# EM2.net
KiCad netlist of a schematic drawn in EAGLE
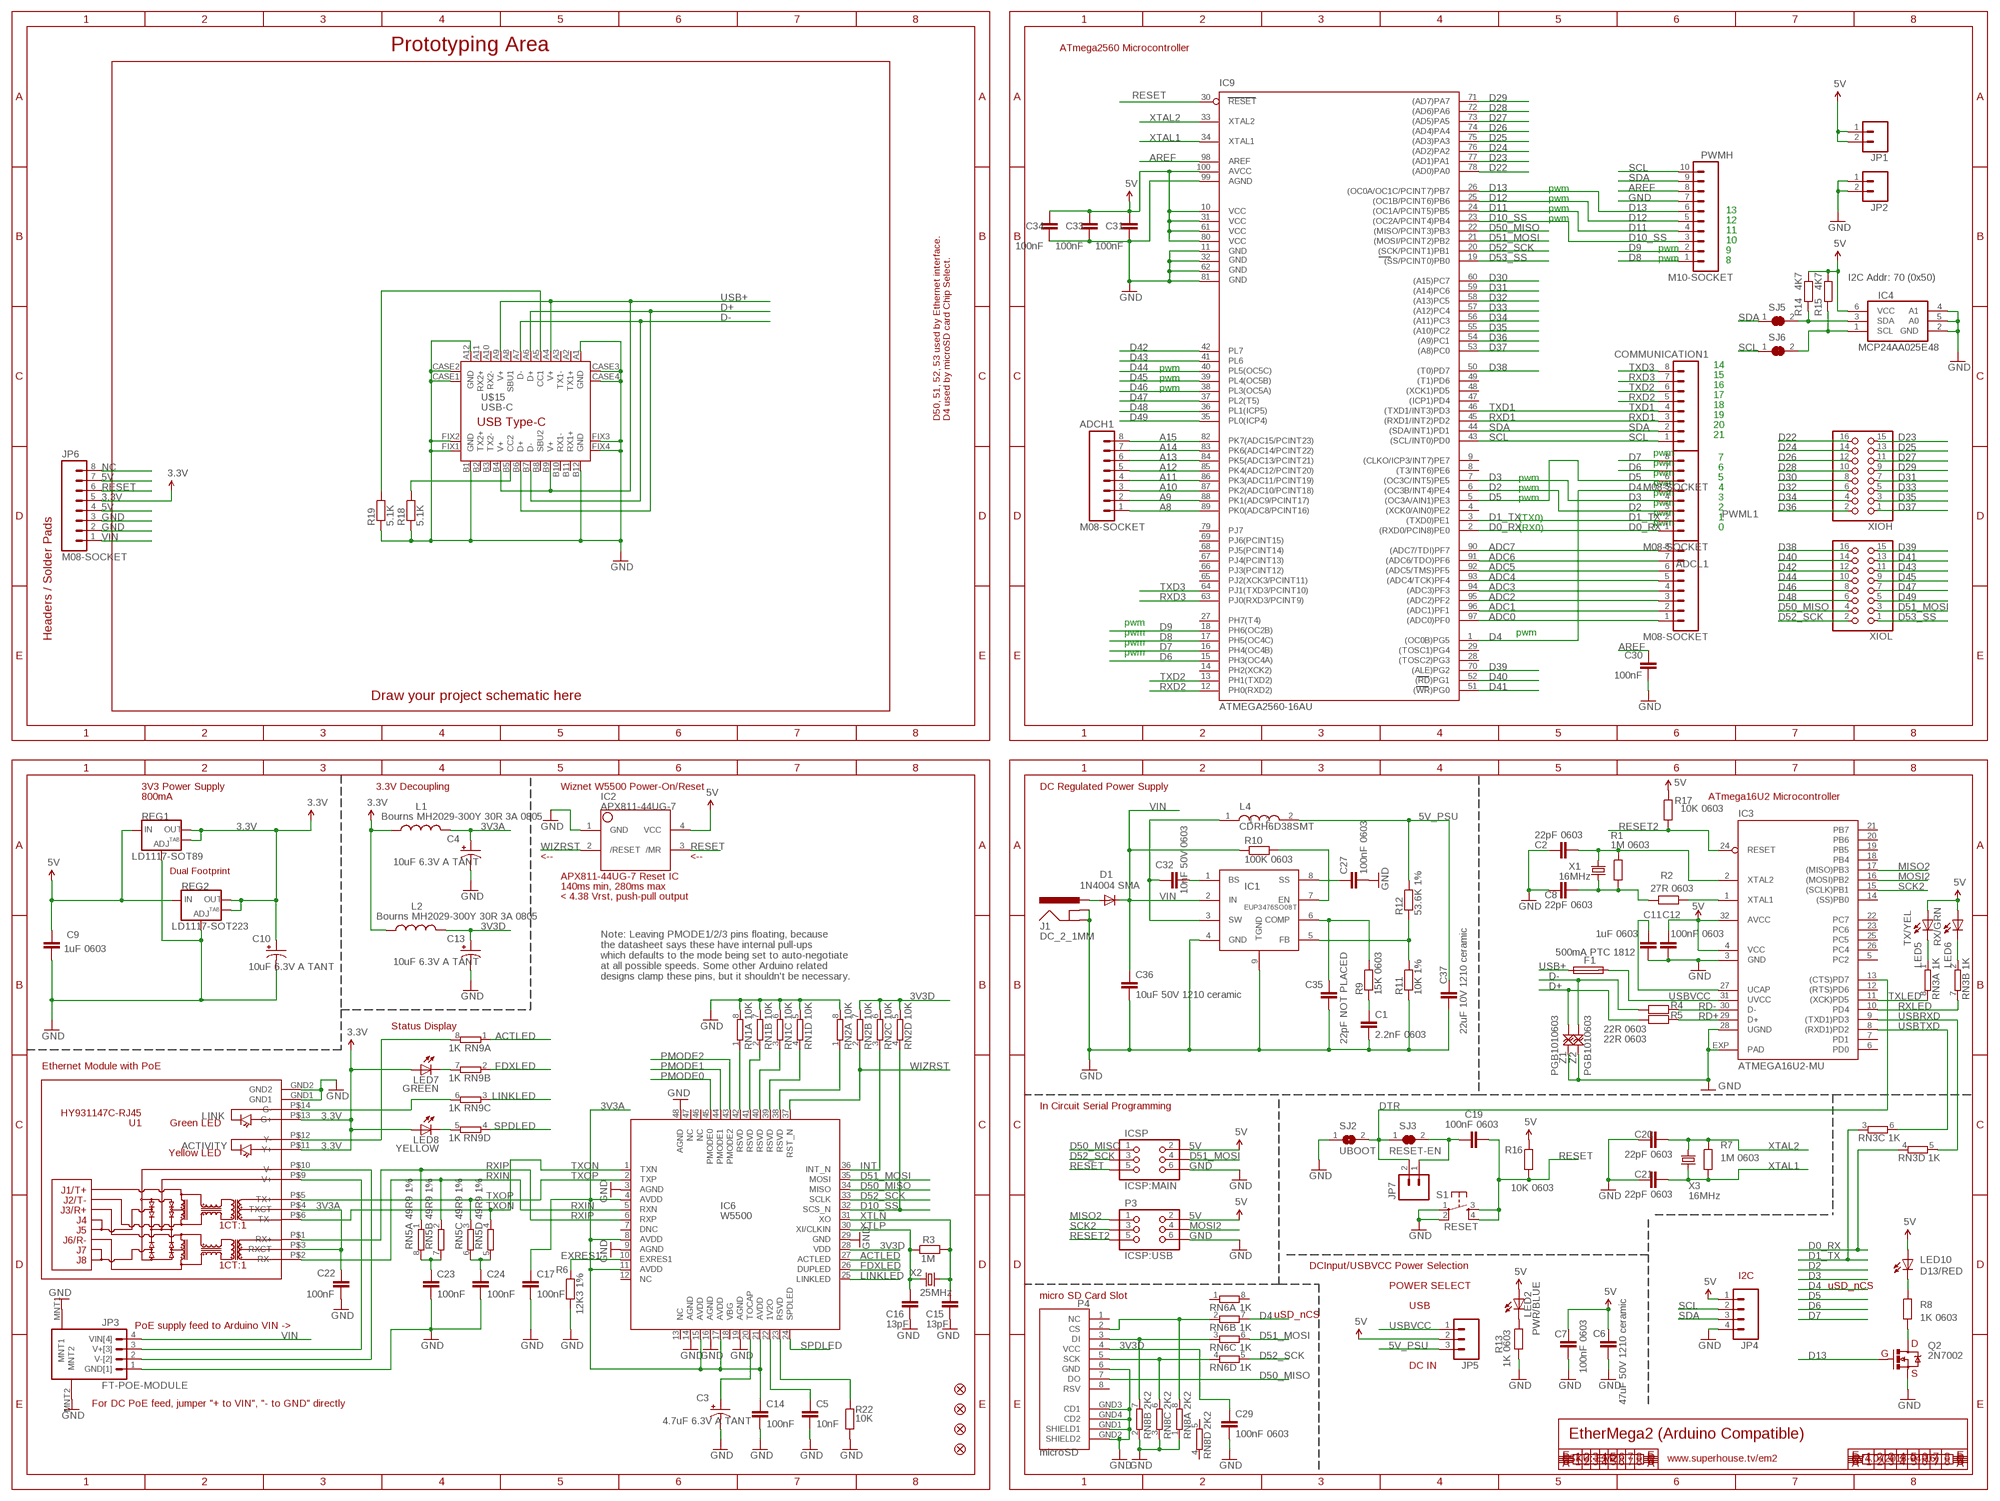
[diagram p0: schematic, sheet 1]

(export (version "E")
  (design (tool "Eeschema 10.0.6"))
  (components
    (comp (ref "ADCH1")
      (value "M08-SOCKET")
      (footprint "eagle-import:1X08-S")
      (libsource (lib "eagle-import") (part "M08-SOCKET"))
    )
    (comp (ref "ADCL1")
      (value "M08-SOCKET")
      (footprint "eagle-import:1X08-S")
      (libsource (lib "eagle-import") (part "M08-SOCKET"))
    )
    (comp (ref "C1")
      (value "2.2nF 0603")
      (footprint "eagle-import:C0603")
      (libsource (lib "eagle-import") (part "CAP0603"))
    )
    (comp (ref "C2")
      (value "22pF 0603")
      (footprint "eagle-import:C0603")
      (libsource (lib "eagle-import") (part "CAP0603"))
    )
    (comp (ref "C3")
      (value "4.7uF 6.3V A TANT")
      (footprint "eagle-import:EIA3216")
      (libsource (lib "eagle-import") (part "CAP_POL1206"))
    )
    (comp (ref "C4")
      (value "10uF 6.3V A TANT")
      (footprint "eagle-import:EIA3216")
      (libsource (lib "eagle-import") (part "CAP_POL1206"))
    )
    (comp (ref "C5")
      (value "10nF")
      (footprint "eagle-import:C0603")
      (libsource (lib "eagle-import") (part "CAP0603"))
    )
    (comp (ref "C6")
      (value "47uF 50V 1210 ceramic")
      (footprint "eagle-import:C1210")
      (libsource (lib "eagle-import") (part "C-EUC1210"))
    )
    (comp (ref "C7")
      (value "100nF 0603")
      (footprint "eagle-import:C0603")
      (libsource (lib "eagle-import") (part "CAP0603"))
    )
    (comp (ref "C8")
      (value "22pF 0603")
      (footprint "eagle-import:C0603")
      (libsource (lib "eagle-import") (part "CAP0603"))
    )
    (comp (ref "C9")
      (value "1uF 0603")
      (footprint "eagle-import:C0603")
      (libsource (lib "eagle-import") (part "CAP0603"))
    )
    (comp (ref "C10")
      (value "10uF 6.3V A TANT")
      (footprint "eagle-import:EIA3216")
      (libsource (lib "eagle-import") (part "CAP_POL1206"))
    )
    (comp (ref "C11")
      (value "1uF 0603")
      (footprint "eagle-import:C0603")
      (libsource (lib "eagle-import") (part "CAP0603"))
    )
    (comp (ref "C12")
      (value "100nF 0603")
      (footprint "eagle-import:C0603")
      (libsource (lib "eagle-import") (part "CAP0603"))
    )
    (comp (ref "C13")
      (value "10uF 6.3V A TANT")
      (footprint "eagle-import:EIA3216")
      (libsource (lib "eagle-import") (part "CAP_POL1206"))
    )
    (comp (ref "C14")
      (value "100nF")
      (footprint "eagle-import:C0603")
      (libsource (lib "eagle-import") (part "CAP0603"))
    )
    (comp (ref "C15")
      (value "13pF")
      (footprint "eagle-import:C0603")
      (libsource (lib "eagle-import") (part "CAP0603"))
    )
    (comp (ref "C16")
      (value "13pF")
      (footprint "eagle-import:C0603")
      (libsource (lib "eagle-import") (part "CAP0603"))
    )
    (comp (ref "C17")
      (value "100nF")
      (footprint "eagle-import:C0603")
      (libsource (lib "eagle-import") (part "CAP0603"))
    )
    (comp (ref "C19")
      (value "100nF 0603")
      (footprint "eagle-import:C0603")
      (libsource (lib "eagle-import") (part "CAP0603"))
    )
    (comp (ref "C20")
      (value "22pF 0603")
      (footprint "eagle-import:C0603")
      (libsource (lib "eagle-import") (part "CAP0603"))
    )
    (comp (ref "C21")
      (value "22pF 0603")
      (footprint "eagle-import:C0603")
      (libsource (lib "eagle-import") (part "CAP0603"))
    )
    (comp (ref "C22")
      (value "100nF")
      (footprint "eagle-import:C0603")
      (libsource (lib "eagle-import") (part "CAP0603"))
    )
    (comp (ref "C23")
      (value "100nF")
      (footprint "eagle-import:C0603")
      (libsource (lib "eagle-import") (part "CAP0603"))
    )
    (comp (ref "C24")
      (value "100nF")
      (footprint "eagle-import:C0603")
      (libsource (lib "eagle-import") (part "CAP0603"))
    )
    (comp (ref "C27")
      (value "100nF 0603")
      (footprint "eagle-import:C0603")
      (libsource (lib "eagle-import") (part "CAP0603"))
    )
    (comp (ref "C29")
      (value "100nF 0603")
      (footprint "eagle-import:C0603")
      (libsource (lib "eagle-import") (part "CAP0603"))
    )
    (comp (ref "C30")
      (value "100nF")
      (footprint "eagle-import:C0603")
      (libsource (lib "eagle-import") (part "CAP0603"))
    )
    (comp (ref "C31")
      (value "100nF")
      (footprint "eagle-import:C0603")
      (libsource (lib "eagle-import") (part "CAP0603"))
    )
    (comp (ref "C32")
      (value "10nF 50V 0603")
      (footprint "eagle-import:C0603")
      (libsource (lib "eagle-import") (part "CAP0603"))
    )
    (comp (ref "C33")
      (value "100nF")
      (footprint "eagle-import:C0603")
      (libsource (lib "eagle-import") (part "CAP0603"))
    )
    (comp (ref "C34")
      (value "100nF")
      (footprint "eagle-import:C0603")
      (libsource (lib "eagle-import") (part "CAP0603"))
    )
    (comp (ref "C35")
      (value "22pF NOT PLACED")
      (footprint "eagle-import:C0603")
      (libsource (lib "eagle-import") (part "CAP0603"))
    )
    (comp (ref "C36")
      (value "10uF 50V 1210 ceramic")
      (footprint "eagle-import:C1210")
      (libsource (lib "eagle-import") (part "C-EUC1210"))
    )
    (comp (ref "C37")
      (value "22uF 10V 1210 ceramic")
      (footprint "eagle-import:C1210")
      (libsource (lib "eagle-import") (part "C-EUC1210"))
    )
    (comp (ref "COMMUNICATION1")
      (value "M08-SOCKET")
      (footprint "eagle-import:1X08-S")
      (libsource (lib "eagle-import") (part "M08-SOCKET"))
    )
    (comp (ref "D1")
      (value "1N4004 SMA")
      (footprint "eagle-import:SMA-DIODE")
      (libsource (lib "eagle-import") (part "DIODESMA"))
    )
    (comp (ref "F1")
      (value "500mA PTC 1812")
      (footprint "eagle-import:1812")
      (libsource (lib "eagle-import") (part "PTC050"))
    )
    (comp (ref "FID1")
      (value "FIDUCIAL1X2.5")
      (footprint "eagle-import:FIDUCIAL-1X2.5")
      (libsource (lib "eagle-import") (part "FIDUCIAL1X2.5"))
    )
    (comp (ref "FID2")
      (value "FIDUCIAL1X2.5")
      (footprint "eagle-import:FIDUCIAL-1X2.5")
      (libsource (lib "eagle-import") (part "FIDUCIAL1X2.5"))
    )
    (comp (ref "FID3")
      (value "FIDUCIAL1X2.5")
      (footprint "eagle-import:FIDUCIAL-1X2.5")
      (libsource (lib "eagle-import") (part "FIDUCIAL1X2.5"))
    )
    (comp (ref "FID4")
      (value "FIDUCIAL1X2.5")
      (footprint "eagle-import:FIDUCIAL-1X2.5")
      (libsource (lib "eagle-import") (part "FIDUCIAL1X2.5"))
    )
    (comp (ref "IC1")
      (value "EUP3476SO08T")
      (footprint "eagle-import:SO08T")
      (libsource (lib "eagle-import") (part "EUP3476SO08T"))
    )
    (comp (ref "IC2")
      (value "APX811-44UG-7")
      (footprint "eagle-import:SOT143-R")
      (libsource (lib "eagle-import") (part "APX81X-RESET-IC"))
    )
    (comp (ref "IC3")
      (value "ATMEGA16U2-MU")
      (footprint "eagle-import:ATMEL_QFN32")
      (libsource (lib "eagle-import") (part "ATMEL_ATMEGA8U2-MUQFN"))
    )
    (comp (ref "IC4")
      (value "MCP24AA025E48")
      (footprint "eagle-import:SOT23-6")
      (libsource (lib "eagle-import") (part "MCP24AA025E48"))
    )
    (comp (ref "IC6")
      (value "W5500")
      (footprint "eagle-import:W5500")
      (libsource (lib "eagle-import") (part "W5500"))
    )
    (comp (ref "IC9")
      (value "ATMEGA2560-16AU")
      (footprint "eagle-import:TQFP100")
      (libsource (lib "eagle-import") (part "ATMEGA2560AU2560-16"))
    )
    (comp (ref "ICSP")
      (value "ICSP:MAIN")
      (footprint "eagle-import:2X03-ICSP")
      (libsource (lib "eagle-import") (part "ICSP-PIN"))
    )
    (comp (ref "J1")
      (value "DC_2_1MM")
      (footprint "eagle-import:POWER_JACK_SLOTS")
      (libsource (lib "eagle-import") (part "POWER_JACK-SLOTS"))
    )
    (comp (ref "JP1")
      (value "M02PTH")
      (footprint "eagle-import:1X02")
      (libsource (lib "eagle-import") (part "M02PTH"))
    )
    (comp (ref "JP2")
      (value "M02PTH")
      (footprint "eagle-import:1X02")
      (libsource (lib "eagle-import") (part "M02PTH"))
    )
    (comp (ref "JP3")
      (value "FT-POE-MODULE")
      (footprint "eagle-import:FT-POE-MODULE-CLEAN")
      (libsource (lib "eagle-import") (part "FT-POE-MODULE2"))
    )
    (comp (ref "JP4")
      (value "M04PTH")
      (footprint "eagle-import:1X04")
      (libsource (lib "eagle-import") (part "M04PTH"))
    )
    (comp (ref "JP5")
      (value "M03-PIN")
      (footprint "eagle-import:1X03-P")
      (libsource (lib "eagle-import") (part "M03-PIN"))
    )
    (comp (ref "JP6")
      (value "M08-SOCKET")
      (footprint "eagle-import:1X08-S")
      (libsource (lib "eagle-import") (part "M08-SOCKET"))
    )
    (comp (ref "JP7")
      (value "M02PTH")
      (footprint "eagle-import:1X02")
      (libsource (lib "eagle-import") (part "freetronics-master-v1.1_M02PTH"))
    )
    (comp (ref "L1")
      (value "Bourns MH2029-300Y 30R 3A 0805")
      (footprint "eagle-import:L2012C")
      (libsource (lib "eagle-import") (part "L-USL2012C"))
    )
    (comp (ref "L2")
      (value "Bourns MH2029-300Y 30R 3A 0805")
      (footprint "eagle-import:L2012C")
      (libsource (lib "eagle-import") (part "L-USL2012C"))
    )
    (comp (ref "L4")
      (value "CDRH6D38SMT")
      (footprint "eagle-import:CDRH")
      (libsource (lib "eagle-import") (part "CDRH6D38SMT"))
    )
    (comp (ref "LED2")
      (value "PWR/BLUE")
      (footprint "eagle-import:LED-0603")
      (libsource (lib "eagle-import") (part "LED0603"))
    )
    (comp (ref "LED5")
      (value "TX/YEL")
      (footprint "eagle-import:LED-0603")
      (libsource (lib "eagle-import") (part "LED0603"))
    )
    (comp (ref "LED6")
      (value "RX/GRN")
      (footprint "eagle-import:LED-0603")
      (libsource (lib "eagle-import") (part "LED0603"))
    )
    (comp (ref "LED7")
      (value "GREEN")
      (footprint "eagle-import:LED-0603")
      (libsource (lib "eagle-import") (part "LED0603"))
    )
    (comp (ref "LED8")
      (value "YELLOW")
      (footprint "eagle-import:LED-0603")
      (libsource (lib "eagle-import") (part "LED0603"))
    )
    (comp (ref "LED10")
      (value "D13/RED")
      (footprint "eagle-import:LED-0603")
      (libsource (lib "eagle-import") (part "LED0603"))
    )
    (comp (ref "P3")
      (value "ICSP:USB")
      (footprint "eagle-import:2X03-ICSP")
      (libsource (lib "eagle-import") (part "ICSP-PIN"))
    )
    (comp (ref "P4")
      (value "microSD")
      (footprint "eagle-import:MOLEX-SD-500901-003")
      (libsource (lib "eagle-import") (part "USD-SOCKETHINGE"))
    )
    (comp (ref "PWMH")
      (value "M10-SOCKET")
      (footprint "eagle-import:1X10-S")
      (libsource (lib "eagle-import") (part "M10-SOCKET"))
    )
    (comp (ref "PWML1")
      (value "M08-SOCKET")
      (footprint "eagle-import:1X08-S")
      (libsource (lib "eagle-import") (part "M08-SOCKET"))
    )
    (comp (ref "Q2")
      (value "2N7002")
      (footprint "eagle-import:SOT23-3")
      (libsource (lib "eagle-import") (part "MOSFET-NCHANNEL-233"))
    )
    (comp (ref "R1")
      (value "1M 0603")
      (footprint "eagle-import:R0603")
      (libsource (lib "eagle-import") (part "RESISTOR0603"))
    )
    (comp (ref "R2")
      (value "27R 0603")
      (footprint "eagle-import:R0603")
      (libsource (lib "eagle-import") (part "RESISTOR0603"))
    )
    (comp (ref "R3")
      (value "1M")
      (footprint "eagle-import:R0603")
      (libsource (lib "eagle-import") (part "RESISTOR0603"))
    )
    (comp (ref "R4")
      (value "22R 0603")
      (footprint "eagle-import:R0603")
      (libsource (lib "eagle-import") (part "RESISTOR0603"))
    )
    (comp (ref "R5")
      (value "22R 0603")
      (footprint "eagle-import:R0603")
      (libsource (lib "eagle-import") (part "RESISTOR0603"))
    )
    (comp (ref "R6")
      (value "12K3 1%")
      (footprint "eagle-import:R0603")
      (libsource (lib "eagle-import") (part "RESISTOR0603"))
    )
    (comp (ref "R7")
      (value "1M 0603")
      (footprint "eagle-import:R0603")
      (libsource (lib "eagle-import") (part "RESISTOR0603"))
    )
    (comp (ref "R8")
      (value "1K 0603")
      (footprint "eagle-import:R0603")
      (libsource (lib "eagle-import") (part "RESISTOR0603"))
    )
    (comp (ref "R9")
      (value "15K 0603")
      (footprint "eagle-import:R0603")
      (libsource (lib "eagle-import") (part "RESISTOR0603"))
    )
    (comp (ref "R10")
      (value "100K 0603")
      (footprint "eagle-import:R0603")
      (libsource (lib "eagle-import") (part "RESISTOR0603"))
    )
    (comp (ref "R11")
      (value "10K 1%")
      (footprint "eagle-import:R0603")
      (libsource (lib "eagle-import") (part "RESISTOR0603"))
    )
    (comp (ref "R12")
      (value "53.6K 1%")
      (footprint "eagle-import:R0603")
      (libsource (lib "eagle-import") (part "RESISTOR0603"))
    )
    (comp (ref "R13")
      (value "1K 0603")
      (footprint "eagle-import:R0603")
      (libsource (lib "eagle-import") (part "RESISTOR0603"))
    )
    (comp (ref "R14")
      (value "4K7")
      (footprint "eagle-import:R0603")
      (libsource (lib "eagle-import") (part "RESISTOR0603"))
    )
    (comp (ref "R15")
      (value "4K7")
      (footprint "eagle-import:R0603")
      (libsource (lib "eagle-import") (part "RESISTOR0603"))
    )
    (comp (ref "R16")
      (value "10K 0603")
      (footprint "eagle-import:R0603")
      (libsource (lib "eagle-import") (part "RESISTOR0603"))
    )
    (comp (ref "R17")
      (value "10K 0603")
      (footprint "eagle-import:R0603")
      (libsource (lib "eagle-import") (part "RESISTOR0603"))
    )
    (comp (ref "R18")
      (value "5.1K")
      (footprint "eagle-import:R0603")
      (libsource (lib "eagle-import") (part "RESISTOR0603"))
    )
    (comp (ref "R19")
      (value "5.1K")
      (footprint "eagle-import:R0603")
      (libsource (lib "eagle-import") (part "RESISTOR0603"))
    )
    (comp (ref "R22")
      (value "10K")
      (footprint "eagle-import:R0603")
      (libsource (lib "eagle-import") (part "RESISTOR0603"))
    )
    (comp (ref "REG1")
      (value "LD1117-SOT89")
      (footprint "eagle-import:SOT89")
      (libsource (lib "eagle-import") (part "V_REG_LM1117SOT89"))
    )
    (comp (ref "REG2")
      (value "LD1117-SOT223")
      (footprint "eagle-import:SOT223")
      (libsource (lib "eagle-import") (part "V_REG_LM1117SOT223"))
    )
    (comp (ref "RN1")
      (value "10K")
      (footprint "eagle-import:CAY16")
      (libsource (lib "eagle-import") (part "4R-NCAY16"))
    )
    (comp (ref "RN2")
      (value "10K")
      (footprint "eagle-import:CAY16")
      (libsource (lib "eagle-import") (part "4R-NCAY16"))
    )
    (comp (ref "RN3")
      (value "1K")
      (footprint "eagle-import:CAY16")
      (libsource (lib "eagle-import") (part "4R-NCAY16"))
    )
    (comp (ref "RN5")
      (value "49R9 1%")
      (footprint "eagle-import:CAY16")
      (libsource (lib "eagle-import") (part "4R-NCAY16"))
    )
    (comp (ref "RN6")
      (value "1K")
      (footprint "eagle-import:CAY16")
      (libsource (lib "eagle-import") (part "4R-NCAY16"))
    )
    (comp (ref "RN8")
      (value "2K2")
      (footprint "eagle-import:CAY16")
      (libsource (lib "eagle-import") (part "4R-NCAY16"))
    )
    (comp (ref "RN9")
      (value "1K")
      (footprint "eagle-import:CAY16")
      (libsource (lib "eagle-import") (part "4R-NCAY16"))
    )
    (comp (ref "S1")
      (value "RESET")
      (footprint "eagle-import:TACTILE_SMT-6MM")
      (libsource (lib "eagle-import") (part "TAC_SWITCH-SMT-6"))
    )
    (comp (ref "SJ2")
      (value "UBOOT")
      (footprint "eagle-import:SJ")
      (libsource (lib "eagle-import") (part "SJ"))
    )
    (comp (ref "SJ3")
      (value "RESET-EN")
      (footprint "eagle-import:SJC")
      (libsource (lib "eagle-import") (part "SJCN"))
    )
    (comp (ref "SJ5")
      (value "SJCN")
      (footprint "eagle-import:SJC")
      (libsource (lib "eagle-import") (part "SJCN"))
    )
    (comp (ref "SJ6")
      (value "SJCN")
      (footprint "eagle-import:SJC")
      (libsource (lib "eagle-import") (part "SJCN"))
    )
    (comp (ref "U$15")
      (value "USB-C")
      (footprint "eagle-import:USB-C-U52A")
      (libsource (lib "eagle-import") (part "USB-C"))
    )
    (comp (ref "U1")
      (value "HY931147C-RJ45")
      (footprint "eagle-import:HY931147C")
      (libsource (lib "eagle-import") (part "HY931147C-RJ45"))
    )
    (comp (ref "X1")
      (value "16MHz")
      (footprint "eagle-import:HC49U-V")
      (libsource (lib "eagle-import") (part "CRYSTALHC49UV"))
    )
    (comp (ref "X2")
      (value "25MHz")
      (footprint "eagle-import:HC49U-V")
      (libsource (lib "eagle-import") (part "CRYSTALHC49UV"))
    )
    (comp (ref "X3")
      (value "16MHz")
      (footprint "eagle-import:HC49U-V")
      (libsource (lib "eagle-import") (part "CRYSTALHC49UV"))
    )
    (comp (ref "XIOH")
      (value "PINHD-2X8")
      (footprint "eagle-import:2X08")
      (libsource (lib "eagle-import") (part "PINHD-2X8"))
    )
    (comp (ref "XIOL")
      (value "PINHD-2X8")
      (footprint "eagle-import:2X08")
      (libsource (lib "eagle-import") (part "PINHD-2X8"))
    )
    (comp (ref "Z1")
      (value "PGB1010603")
      (footprint "eagle-import:TVS0603")
      (libsource (lib "eagle-import") (part "TVS0603"))
    )
    (comp (ref "Z2")
      (value "PGB1010603")
      (footprint "eagle-import:TVS0603")
      (libsource (lib "eagle-import") (part "TVS0603"))
    )
  )
  (nets
    (net (code "1") (name "/3V3A") (class "Default")
      (node (ref "C14") (pin "1") (pinfunction "1_1") (pintype "passive"))
      (node (ref "C17") (pin "1") (pinfunction "1_1") (pintype "passive"))
      (node (ref "C22") (pin "1") (pinfunction "1_1") (pintype "passive"))
      (node (ref "C4") (pin "A") (pinfunction "+_A") (pintype "passive"))
      (node (ref "IC6") (pin "11") (pinfunction "AVDD_11") (pintype "passive"))
      (node (ref "IC6") (pin "15") (pinfunction "AVDD_15") (pintype "passive"))
      (node (ref "IC6") (pin "17") (pinfunction "AVDD_17") (pintype "passive"))
      (node (ref "IC6") (pin "21") (pinfunction "AVDD_21") (pintype "passive"))
      (node (ref "IC6") (pin "4") (pinfunction "AVDD_4") (pintype "passive"))
      (node (ref "IC6") (pin "8") (pinfunction "AVDD_8") (pintype "passive"))
      (node (ref "L1") (pin "2") (pinfunction "2_2") (pintype "passive"))
      (node (ref "U1") (pin "P$3") (pinfunction "RXCT_P$3") (pintype "bidirectional"))
      (node (ref "U1") (pin "P$4") (pinfunction "TXCT_P$4") (pintype "bidirectional"))
    )
    (net (code "2") (name "/3V3D") (class "Default")
      (node (ref "C13") (pin "A") (pinfunction "+_A") (pintype "passive"))
      (node (ref "C29") (pin "1") (pinfunction "1_1") (pintype "passive"))
      (node (ref "IC6") (pin "28") (pinfunction "VDD_28") (pintype "passive"))
      (node (ref "L2") (pin "2") (pinfunction "2_2") (pintype "passive"))
      (node (ref "P4") (pin "4") (pinfunction "VCC_4") (pintype "bidirectional"))
      (node (ref "RN2") (pin "5") (pinfunction "2_5") (pintype "passive"))
      (node (ref "RN2") (pin "6") (pinfunction "2_6") (pintype "passive"))
      (node (ref "RN2") (pin "7") (pinfunction "2_7") (pintype "passive"))
    )
    (net (code "3") (name "/5V_PSU") (class "Default")
      (node (ref "C37") (pin "1") (pinfunction "1_1") (pintype "passive"))
      (node (ref "JP5") (pin "3") (pinfunction "3_3") (pintype "passive"))
      (node (ref "L4") (pin "2") (pinfunction "2_2") (pintype "bidirectional"))
      (node (ref "R12") (pin "2") (pinfunction "2_2") (pintype "passive"))
    )
    (net (code "4") (name "/A8") (class "Default")
      (node (ref "ADCH1") (pin "1") (pinfunction "1_1") (pintype "passive"))
      (node (ref "IC9") (pin "89") (pinfunction "PK0(ADC8/PCINT16)_89") (pintype "bidirectional"))
    )
    (net (code "5") (name "/A9") (class "Default")
      (node (ref "ADCH1") (pin "2") (pinfunction "2_2") (pintype "passive"))
      (node (ref "IC9") (pin "88") (pinfunction "PK1(ADC9/PCINT17)_88") (pintype "bidirectional"))
    )
    (net (code "6") (name "/A10") (class "Default")
      (node (ref "ADCH1") (pin "3") (pinfunction "3_3") (pintype "passive"))
      (node (ref "IC9") (pin "87") (pinfunction "PK2(ADC10/PCINT18)_87") (pintype "bidirectional"))
    )
    (net (code "7") (name "/A11") (class "Default")
      (node (ref "ADCH1") (pin "4") (pinfunction "4_4") (pintype "passive"))
      (node (ref "IC9") (pin "86") (pinfunction "PK3(ADC11/PCINT19)_86") (pintype "bidirectional"))
    )
    (net (code "8") (name "/A12") (class "Default")
      (node (ref "ADCH1") (pin "5") (pinfunction "5_5") (pintype "passive"))
      (node (ref "IC9") (pin "85") (pinfunction "PK4(ADC12/PCINT20)_85") (pintype "bidirectional"))
    )
    (net (code "9") (name "/A13") (class "Default")
      (node (ref "ADCH1") (pin "6") (pinfunction "6_6") (pintype "passive"))
      (node (ref "IC9") (pin "84") (pinfunction "PK5(ADC13/PCINT21)_84") (pintype "bidirectional"))
    )
    (net (code "10") (name "/A14") (class "Default")
      (node (ref "ADCH1") (pin "7") (pinfunction "7_7") (pintype "passive"))
      (node (ref "IC9") (pin "83") (pinfunction "PK6(ADC14/PCINT22)_83") (pintype "bidirectional"))
    )
    (net (code "11") (name "/A15") (class "Default")
      (node (ref "ADCH1") (pin "8") (pinfunction "8_8") (pintype "passive"))
      (node (ref "IC9") (pin "82") (pinfunction "PK7(ADC15/PCINT23)_82") (pintype "bidirectional"))
    )
    (net (code "12") (name "/ACTLED") (class "Default")
      (node (ref "IC6") (pin "27") (pinfunction "ACTLED_27") (pintype "passive"))
      (node (ref "RN9") (pin "1") (pinfunction "1_1") (pintype "passive"))
    )
    (net (code "13") (name "/ADC0") (class "Default")
      (node (ref "ADCL1") (pin "1") (pinfunction "1_1") (pintype "passive"))
      (node (ref "IC9") (pin "97") (pinfunction "(ADC0)PF0_97") (pintype "bidirectional"))
    )
    (net (code "14") (name "/ADC1") (class "Default")
      (node (ref "ADCL1") (pin "2") (pinfunction "2_2") (pintype "passive"))
      (node (ref "IC9") (pin "96") (pinfunction "(ADC1)PF1_96") (pintype "bidirectional"))
    )
    (net (code "15") (name "/ADC2") (class "Default")
      (node (ref "ADCL1") (pin "3") (pinfunction "3_3") (pintype "passive"))
      (node (ref "IC9") (pin "95") (pinfunction "(ADC2)PF2_95") (pintype "bidirectional"))
    )
    (net (code "16") (name "/ADC3") (class "Default")
      (node (ref "ADCL1") (pin "4") (pinfunction "4_4") (pintype "passive"))
      (node (ref "IC9") (pin "94") (pinfunction "(ADC3)PF3_94") (pintype "bidirectional"))
    )
    (net (code "17") (name "/ADC4") (class "Default")
      (node (ref "ADCL1") (pin "5") (pinfunction "5_5") (pintype "passive"))
      (node (ref "IC9") (pin "93") (pinfunction "(ADC4/TCK)PF4_93") (pintype "bidirectional"))
    )
    (net (code "18") (name "/ADC5") (class "Default")
      (node (ref "ADCL1") (pin "6") (pinfunction "6_6") (pintype "passive"))
      (node (ref "IC9") (pin "92") (pinfunction "(ADC5/TMS)PF5_92") (pintype "bidirectional"))
    )
    (net (code "19") (name "/ADC6") (class "Default")
      (node (ref "ADCL1") (pin "7") (pinfunction "7_7") (pintype "passive"))
      (node (ref "IC9") (pin "91") (pinfunction "(ADC6/TDO)PF6_91") (pintype "bidirectional"))
    )
    (net (code "20") (name "/ADC7") (class "Default")
      (node (ref "ADCL1") (pin "8") (pinfunction "8_8") (pintype "passive"))
      (node (ref "IC9") (pin "90") (pinfunction "(ADC7/TDI)PF7_90") (pintype "bidirectional"))
    )
    (net (code "21") (name "/AREF") (class "Default")
      (node (ref "C30") (pin "1") (pinfunction "1_1") (pintype "passive"))
      (node (ref "IC9") (pin "98") (pinfunction "AREF_98") (pintype "bidirectional"))
      (node (ref "PWMH") (pin "8") (pinfunction "8_8") (pintype "passive"))
    )
    (net (code "22") (name "/D+") (class "Default")
      (node (ref "R5") (pin "2") (pinfunction "2_2") (pintype "passive"))
      (node (ref "U$15") (pin "A6") (pinfunction "D+_A6") (pintype "bidirectional"))
      (node (ref "U$15") (pin "B6") (pinfunction "D+_B6") (pintype "bidirectional"))
      (node (ref "Z1") (pin "1") (pinfunction "1_1") (pintype "passive"))
    )
    (net (code "23") (name "/D-") (class "Default")
      (node (ref "R4") (pin "2") (pinfunction "2_2") (pintype "passive"))
      (node (ref "U$15") (pin "A7") (pinfunction "D-_A7") (pintype "bidirectional"))
      (node (ref "U$15") (pin "B7") (pinfunction "D-_B7") (pintype "bidirectional"))
      (node (ref "Z2") (pin "1") (pinfunction "1_1") (pintype "passive"))
    )
    (net (code "24") (name "/D0_RX") (class "Default")
      (node (ref "IC9") (pin "2") (pinfunction "(RXD0/PCIN8)PE0_2") (pintype "bidirectional"))
      (node (ref "PWML1") (pin "1") (pinfunction "1_1") (pintype "passive"))
      (node (ref "RN3") (pin "4") (pinfunction "1_4") (pintype "passive"))
    )
    (net (code "25") (name "/D1_TX") (class "Default")
      (node (ref "IC9") (pin "3") (pinfunction "(TXD0)PE1_3") (pintype "bidirectional"))
      (node (ref "PWML1") (pin "2") (pinfunction "2_2") (pintype "passive"))
      (node (ref "RN3") (pin "3") (pinfunction "1_3") (pintype "passive"))
    )
    (net (code "26") (name "/D2") (class "Default")
      (node (ref "IC9") (pin "6") (pinfunction "(OC3B/INT4)PE4_6") (pintype "bidirectional"))
      (node (ref "PWML1") (pin "3") (pinfunction "3_3") (pintype "passive"))
    )
    (net (code "27") (name "/D3") (class "Default")
      (node (ref "IC9") (pin "7") (pinfunction "(OC3C/INT5)PE5_7") (pintype "bidirectional"))
      (node (ref "PWML1") (pin "4") (pinfunction "4_4") (pintype "passive"))
    )
    (net (code "28") (name "/D4") (class "Default")
      (node (ref "IC9") (pin "1") (pinfunction "(OC0B)PG5_1") (pintype "bidirectional"))
      (node (ref "PWML1") (pin "5") (pinfunction "5_5") (pintype "passive"))
      (node (ref "RN6") (pin "7") (pinfunction "2_7") (pintype "passive"))
    )
    (net (code "29") (name "/D5") (class "Default")
      (node (ref "IC9") (pin "5") (pinfunction "(OC3A/AIN1)PE3_5") (pintype "bidirectional"))
      (node (ref "PWML1") (pin "6") (pinfunction "6_6") (pintype "passive"))
    )
    (net (code "30") (name "/D6") (class "Default")
      (node (ref "IC9") (pin "15") (pinfunction "PH3(OC4A)_15") (pintype "bidirectional"))
      (node (ref "PWML1") (pin "7") (pinfunction "7_7") (pintype "passive"))
    )
    (net (code "31") (name "/D7") (class "Default")
      (node (ref "IC9") (pin "16") (pinfunction "PH4(OC4B)_16") (pintype "bidirectional"))
      (node (ref "PWML1") (pin "8") (pinfunction "8_8") (pintype "passive"))
    )
    (net (code "32") (name "/D8") (class "Default")
      (node (ref "IC9") (pin "17") (pinfunction "PH5(OC4C)_17") (pintype "bidirectional"))
      (node (ref "PWMH") (pin "1") (pinfunction "1_1") (pintype "passive"))
    )
    (net (code "33") (name "/D9") (class "Default")
      (node (ref "IC9") (pin "18") (pinfunction "PH6(OC2B)_18") (pintype "bidirectional"))
      (node (ref "PWMH") (pin "2") (pinfunction "2_2") (pintype "passive"))
    )
    (net (code "34") (name "/D10_SS") (class "Default")
      (node (ref "IC6") (pin "32") (pinfunction "SCS_N_32") (pintype "passive"))
      (node (ref "IC9") (pin "23") (pinfunction "(OC2A/PCINT4)PB4_23") (pintype "bidirectional"))
      (node (ref "PWMH") (pin "3") (pinfunction "3_3") (pintype "passive"))
      (node (ref "RN2") (pin "4") (pinfunction "1_4") (pintype "passive"))
    )
    (net (code "35") (name "/D11") (class "Default")
      (node (ref "IC9") (pin "24") (pinfunction "(OC1A/PCINT5)PB5_24") (pintype "bidirectional"))
      (node (ref "PWMH") (pin "4") (pinfunction "4_4") (pintype "passive"))
    )
    (net (code "36") (name "/D12") (class "Default")
      (node (ref "IC9") (pin "25") (pinfunction "(OC1B/PCINT6)PB6_25") (pintype "bidirectional"))
      (node (ref "PWMH") (pin "5") (pinfunction "5_5") (pintype "passive"))
    )
    (net (code "37") (name "/D13") (class "Default")
      (node (ref "IC9") (pin "26") (pinfunction "(OC0A/OC1C/PCINT7)PB7_26") (pintype "bidirectional"))
      (node (ref "PWMH") (pin "6") (pinfunction "6_6") (pintype "passive"))
      (node (ref "Q2") (pin "1") (pinfunction "G_1") (pintype "passive"))
    )
    (net (code "38") (name "/D22") (class "Default")
      (node (ref "IC9") (pin "78") (pinfunction "(AD0)PA0_78") (pintype "bidirectional"))
      (node (ref "XIOH") (pin "16") (pinfunction "16_16") (pintype "passive"))
    )
    (net (code "39") (name "/D23") (class "Default")
      (node (ref "IC9") (pin "77") (pinfunction "(AD1)PA1_77") (pintype "bidirectional"))
      (node (ref "XIOH") (pin "15") (pinfunction "15_15") (pintype "passive"))
    )
    (net (code "40") (name "/D24") (class "Default")
      (node (ref "IC9") (pin "76") (pinfunction "(AD2)PA2_76") (pintype "bidirectional"))
      (node (ref "XIOH") (pin "14") (pinfunction "14_14") (pintype "passive"))
    )
    (net (code "41") (name "/D25") (class "Default")
      (node (ref "IC9") (pin "75") (pinfunction "(AD3)PA3_75") (pintype "bidirectional"))
      (node (ref "XIOH") (pin "13") (pinfunction "13_13") (pintype "passive"))
    )
    (net (code "42") (name "/D26") (class "Default")
      (node (ref "IC9") (pin "74") (pinfunction "(AD4)PA4_74") (pintype "bidirectional"))
      (node (ref "XIOH") (pin "12") (pinfunction "12_12") (pintype "passive"))
    )
    (net (code "43") (name "/D27") (class "Default")
      (node (ref "IC9") (pin "73") (pinfunction "(AD5)PA5_73") (pintype "bidirectional"))
      (node (ref "XIOH") (pin "11") (pinfunction "11_11") (pintype "passive"))
    )
    (net (code "44") (name "/D28") (class "Default")
      (node (ref "IC9") (pin "72") (pinfunction "(AD6)PA6_72") (pintype "bidirectional"))
      (node (ref "XIOH") (pin "10") (pinfunction "10_10") (pintype "passive"))
    )
    (net (code "45") (name "/D29") (class "Default")
      (node (ref "IC9") (pin "71") (pinfunction "(AD7)PA7_71") (pintype "bidirectional"))
      (node (ref "XIOH") (pin "9") (pinfunction "9_9") (pintype "passive"))
    )
    (net (code "46") (name "/D30") (class "Default")
      (node (ref "IC9") (pin "60") (pinfunction "(A15)PC7_60") (pintype "bidirectional"))
      (node (ref "XIOH") (pin "8") (pinfunction "8_8") (pintype "passive"))
    )
    (net (code "47") (name "/D31") (class "Default")
      (node (ref "IC9") (pin "59") (pinfunction "(A14)PC6_59") (pintype "bidirectional"))
      (node (ref "XIOH") (pin "7") (pinfunction "7_7") (pintype "passive"))
    )
    (net (code "48") (name "/D32") (class "Default")
      (node (ref "IC9") (pin "58") (pinfunction "(A13)PC5_58") (pintype "bidirectional"))
      (node (ref "XIOH") (pin "6") (pinfunction "6_6") (pintype "passive"))
    )
    (net (code "49") (name "/D33") (class "Default")
      (node (ref "IC9") (pin "57") (pinfunction "(A12)PC4_57") (pintype "bidirectional"))
      (node (ref "XIOH") (pin "5") (pinfunction "5_5") (pintype "passive"))
    )
    (net (code "50") (name "/D34") (class "Default")
      (node (ref "IC9") (pin "56") (pinfunction "(A11)PC3_56") (pintype "bidirectional"))
      (node (ref "XIOH") (pin "4") (pinfunction "4_4") (pintype "passive"))
    )
    (net (code "51") (name "/D35") (class "Default")
      (node (ref "IC9") (pin "55") (pinfunction "(A10)PC2_55") (pintype "bidirectional"))
      (node (ref "XIOH") (pin "3") (pinfunction "3_3") (pintype "passive"))
    )
    (net (code "52") (name "/D36") (class "Default")
      (node (ref "IC9") (pin "54") (pinfunction "(A9)PC1_54") (pintype "bidirectional"))
      (node (ref "XIOH") (pin "2") (pinfunction "2_2") (pintype "passive"))
    )
    (net (code "53") (name "/D37") (class "Default")
      (node (ref "IC9") (pin "53") (pinfunction "(A8)PC0_53") (pintype "bidirectional"))
      (node (ref "XIOH") (pin "1") (pinfunction "1_1") (pintype "passive"))
    )
    (net (code "54") (name "/D38") (class "Default")
      (node (ref "IC9") (pin "50") (pinfunction "(T0)PD7_50") (pintype "bidirectional"))
      (node (ref "XIOL") (pin "16") (pinfunction "16_16") (pintype "passive"))
    )
    (net (code "55") (name "/D39") (class "Default")
      (node (ref "IC9") (pin "70") (pinfunction "(ALE)PG2_70") (pintype "bidirectional"))
      (node (ref "XIOL") (pin "15") (pinfunction "15_15") (pintype "passive"))
    )
    (net (code "56") (name "/D40") (class "Default")
      (node (ref "IC9") (pin "52") (pinfunction "(RD)PG1_52") (pintype "bidirectional"))
      (node (ref "XIOL") (pin "14") (pinfunction "14_14") (pintype "passive"))
    )
    (net (code "57") (name "/D41") (class "Default")
      (node (ref "IC9") (pin "51") (pinfunction "(WR)PG0_51") (pintype "bidirectional"))
      (node (ref "XIOL") (pin "13") (pinfunction "13_13") (pintype "passive"))
    )
    (net (code "58") (name "/D42") (class "Default")
      (node (ref "IC9") (pin "42") (pinfunction "PL7_42") (pintype "bidirectional"))
      (node (ref "XIOL") (pin "12") (pinfunction "12_12") (pintype "passive"))
    )
    (net (code "59") (name "/D43") (class "Default")
      (node (ref "IC9") (pin "41") (pinfunction "PL6_41") (pintype "bidirectional"))
      (node (ref "XIOL") (pin "11") (pinfunction "11_11") (pintype "passive"))
    )
    (net (code "60") (name "/D44") (class "Default")
      (node (ref "IC9") (pin "40") (pinfunction "PL5(OC5C)_40") (pintype "bidirectional"))
      (node (ref "XIOL") (pin "10") (pinfunction "10_10") (pintype "passive"))
    )
    (net (code "61") (name "/D45") (class "Default")
      (node (ref "IC9") (pin "39") (pinfunction "PL4(OC5B)_39") (pintype "bidirectional"))
      (node (ref "XIOL") (pin "9") (pinfunction "9_9") (pintype "passive"))
    )
    (net (code "62") (name "/D46") (class "Default")
      (node (ref "IC9") (pin "38") (pinfunction "PL3(OC5A)_38") (pintype "bidirectional"))
      (node (ref "XIOL") (pin "8") (pinfunction "8_8") (pintype "passive"))
    )
    (net (code "63") (name "/D47") (class "Default")
      (node (ref "IC9") (pin "37") (pinfunction "PL2(T5)_37") (pintype "bidirectional"))
      (node (ref "XIOL") (pin "7") (pinfunction "7_7") (pintype "passive"))
    )
    (net (code "64") (name "/D48") (class "Default")
      (node (ref "IC9") (pin "36") (pinfunction "PL1(ICP5)_36") (pintype "bidirectional"))
      (node (ref "XIOL") (pin "6") (pinfunction "6_6") (pintype "passive"))
    )
    (net (code "65") (name "/D49") (class "Default")
      (node (ref "IC9") (pin "35") (pinfunction "PL0(ICP4)_35") (pintype "bidirectional"))
      (node (ref "XIOL") (pin "5") (pinfunction "5_5") (pintype "passive"))
    )
    (net (code "66") (name "/D50_MISO") (class "Default")
      (node (ref "IC6") (pin "34") (pinfunction "MISO_34") (pintype "passive"))
      (node (ref "IC9") (pin "22") (pinfunction "(MISO/PCINT3)PB3_22") (pintype "bidirectional"))
      (node (ref "ICSP") (pin "1") (pinfunction "1_1") (pintype "passive"))
      (node (ref "P4") (pin "7") (pinfunction "DO_7") (pintype "bidirectional"))
      (node (ref "XIOL") (pin "4") (pinfunction "4_4") (pintype "passive"))
    )
    (net (code "67") (name "/D51_MOSI") (class "Default")
      (node (ref "IC6") (pin "35") (pinfunction "MOSI_35") (pintype "passive"))
      (node (ref "IC9") (pin "21") (pinfunction "(MOSI/PCINT2)PB2_21") (pintype "bidirectional"))
      (node (ref "ICSP") (pin "4") (pinfunction "4_4") (pintype "passive"))
      (node (ref "RN6") (pin "6") (pinfunction "2_6") (pintype "passive"))
      (node (ref "XIOL") (pin "3") (pinfunction "3_3") (pintype "passive"))
    )
    (net (code "68") (name "/D52_SCK") (class "Default")
      (node (ref "IC6") (pin "33") (pinfunction "SCLK_33") (pintype "passive"))
      (node (ref "IC9") (pin "20") (pinfunction "(SCK/PCINT1)PB1_20") (pintype "bidirectional"))
      (node (ref "ICSP") (pin "3") (pinfunction "3_3") (pintype "passive"))
      (node (ref "RN6") (pin "5") (pinfunction "2_5") (pintype "passive"))
      (node (ref "XIOL") (pin "2") (pinfunction "2_2") (pintype "passive"))
    )
    (net (code "69") (name "/D53_SS") (class "Default")
      (node (ref "IC9") (pin "19") (pinfunction "(SS/PCINT0)PB0_19") (pintype "bidirectional"))
      (node (ref "XIOL") (pin "1") (pinfunction "1_1") (pintype "passive"))
    )
    (net (code "70") (name "/DTR") (class "Default")
      (node (ref "IC3") (pin "13") (pinfunction "(CTS)PD7_13") (pintype "bidirectional"))
      (node (ref "JP7") (pin "2") (pinfunction "2_2") (pintype "passive"))
      (node (ref "SJ2") (pin "2") (pinfunction "2_2") (pintype "passive"))
      (node (ref "SJ3") (pin "1") (pinfunction "1_1") (pintype "passive"))
    )
    (net (code "71") (name "/EXRES1") (class "Default")
      (node (ref "IC6") (pin "10") (pinfunction "EXRES1_10") (pintype "passive"))
      (node (ref "R6") (pin "2") (pinfunction "2_2") (pintype "passive"))
    )
    (net (code "72") (name "/FDXLED") (class "Default")
      (node (ref "IC6") (pin "26") (pinfunction "DUPLED_26") (pintype "passive"))
      (node (ref "RN9") (pin "2") (pinfunction "1_2") (pintype "passive"))
    )
    (net (code "73") (name "/INT") (class "Default")
      (node (ref "IC6") (pin "36") (pinfunction "INT_N_36") (pintype "passive"))
      (node (ref "RN2") (pin "3") (pinfunction "1_3") (pintype "passive"))
    )
    (net (code "74") (name "/LINKLED") (class "Default")
      (node (ref "IC6") (pin "25") (pinfunction "LINKLED_25") (pintype "passive"))
      (node (ref "RN9") (pin "3") (pinfunction "1_3") (pintype "passive"))
    )
    (net (code "75") (name "/MISO2") (class "Default")
      (node (ref "IC3") (pin "17") (pinfunction "(MISO)PB3_17") (pintype "bidirectional"))
      (node (ref "P3") (pin "1") (pinfunction "1_1") (pintype "passive"))
    )
    (net (code "76") (name "/MOSI2") (class "Default")
      (node (ref "IC3") (pin "16") (pinfunction "(MOSI)PB2_16") (pintype "bidirectional"))
      (node (ref "P3") (pin "4") (pinfunction "4_4") (pintype "passive"))
    )
    (net (code "77") (name "/NC") (class "Default")
      (node (ref "JP6") (pin "8") (pinfunction "8_8") (pintype "passive"))
    )
    (net (code "78") (name "/PMODE0") (class "Default")
      (node (ref "IC6") (pin "45") (pinfunction "PMODE0_45") (pintype "passive"))
    )
    (net (code "79") (name "/PMODE1") (class "Default")
      (node (ref "IC6") (pin "44") (pinfunction "PMODE1_44") (pintype "passive"))
    )
    (net (code "80") (name "/PMODE2") (class "Default")
      (node (ref "IC6") (pin "43") (pinfunction "PMODE2_43") (pintype "passive"))
    )
    (net (code "81") (name "/RD+") (class "Default")
      (node (ref "IC3") (pin "29") (pinfunction "D+_29") (pintype "bidirectional"))
      (node (ref "R5") (pin "1") (pinfunction "1_1") (pintype "passive"))
    )
    (net (code "82") (name "/RD-") (class "Default")
      (node (ref "IC3") (pin "30") (pinfunction "D-_30") (pintype "bidirectional"))
      (node (ref "R4") (pin "1") (pinfunction "1_1") (pintype "passive"))
    )
    (net (code "83") (name "/RESET") (class "Default")
      (node (ref "C19") (pin "2") (pinfunction "2_2") (pintype "passive"))
      (node (ref "IC2") (pin "3") (pinfunction "/MR_3") (pintype "input"))
      (node (ref "IC9") (pin "30") (pinfunction "RESET_30") (pintype "input"))
      (node (ref "ICSP") (pin "5") (pinfunction "5_5") (pintype "passive"))
      (node (ref "JP6") (pin "6") (pinfunction "6_6") (pintype "passive"))
      (node (ref "R16") (pin "1") (pinfunction "1_1") (pintype "passive"))
      (node (ref "S1") (pin "3") (pinfunction "3_3") (pintype "passive"))
      (node (ref "S1") (pin "4") (pinfunction "4_4") (pintype "passive"))
    )
    (net (code "84") (name "/RESET2") (class "Default")
      (node (ref "IC3") (pin "24") (pinfunction "RESET_24") (pintype "input"))
      (node (ref "P3") (pin "5") (pinfunction "5_5") (pintype "passive"))
      (node (ref "R17") (pin "1") (pinfunction "1_1") (pintype "passive"))
    )
    (net (code "85") (name "/RXD1") (class "Default")
      (node (ref "COMMUNICATION1") (pin "3") (pinfunction "3_3") (pintype "passive"))
      (node (ref "IC9") (pin "45") (pinfunction "(RXD1/INT2)PD2_45") (pintype "bidirectional"))
    )
    (net (code "86") (name "/RXD2") (class "Default")
      (node (ref "COMMUNICATION1") (pin "5") (pinfunction "5_5") (pintype "passive"))
      (node (ref "IC9") (pin "12") (pinfunction "PH0(RXD2)_12") (pintype "bidirectional"))
    )
    (net (code "87") (name "/RXD3") (class "Default")
      (node (ref "COMMUNICATION1") (pin "7") (pinfunction "7_7") (pintype "passive"))
      (node (ref "IC9") (pin "63") (pinfunction "PJ0(RXD3/PCINT9)_63") (pintype "bidirectional"))
    )
    (net (code "88") (name "/RXIN") (class "Default")
      (node (ref "IC6") (pin "5") (pinfunction "RXN_5") (pintype "passive"))
      (node (ref "RN5") (pin "2") (pinfunction "1_2") (pintype "passive"))
      (node (ref "U1") (pin "P$2") (pinfunction "RX-_P$2") (pintype "bidirectional"))
    )
    (net (code "89") (name "/RXIP") (class "Default")
      (node (ref "IC6") (pin "6") (pinfunction "RXP_6") (pintype "passive"))
      (node (ref "RN5") (pin "1") (pinfunction "1_1") (pintype "passive"))
      (node (ref "U1") (pin "P$1") (pinfunction "RX+_P$1") (pintype "bidirectional"))
    )
    (net (code "90") (name "/RXLED") (class "Default")
      (node (ref "IC3") (pin "10") (pinfunction "PD4_10") (pintype "bidirectional"))
      (node (ref "RN3") (pin "7") (pinfunction "2_7") (pintype "passive"))
    )
    (net (code "91") (name "/SCK2") (class "Default")
      (node (ref "IC3") (pin "15") (pinfunction "(SCLK)PB1_15") (pintype "bidirectional"))
      (node (ref "P3") (pin "3") (pinfunction "3_3") (pintype "passive"))
    )
    (net (code "92") (name "/SCL") (class "Default")
      (node (ref "COMMUNICATION1") (pin "1") (pinfunction "1_1") (pintype "passive"))
      (node (ref "IC9") (pin "43") (pinfunction "(SCL/INT0)PD0_43") (pintype "bidirectional"))
      (node (ref "JP4") (pin "2") (pinfunction "2_2") (pintype "passive"))
      (node (ref "PWMH") (pin "10") (pinfunction "10_10") (pintype "passive"))
      (node (ref "SJ6") (pin "1") (pinfunction "1_1") (pintype "passive"))
    )
    (net (code "93") (name "/SDA") (class "Default")
      (node (ref "COMMUNICATION1") (pin "2") (pinfunction "2_2") (pintype "passive"))
      (node (ref "IC9") (pin "44") (pinfunction "(SDA/INT1)PD1_44") (pintype "bidirectional"))
      (node (ref "JP4") (pin "3") (pinfunction "3_3") (pintype "passive"))
      (node (ref "PWMH") (pin "9") (pinfunction "9_9") (pintype "passive"))
      (node (ref "SJ5") (pin "1") (pinfunction "1_1") (pintype "passive"))
    )
    (net (code "94") (name "/SPDLED") (class "Default")
      (node (ref "IC6") (pin "24") (pinfunction "SPDLED_24") (pintype "passive"))
      (node (ref "RN9") (pin "4") (pinfunction "1_4") (pintype "passive"))
    )
    (net (code "95") (name "/TXD1") (class "Default")
      (node (ref "COMMUNICATION1") (pin "4") (pinfunction "4_4") (pintype "passive"))
      (node (ref "IC9") (pin "46") (pinfunction "(TXD1/INT3)PD3_46") (pintype "bidirectional"))
    )
    (net (code "96") (name "/TXD2") (class "Default")
      (node (ref "COMMUNICATION1") (pin "6") (pinfunction "6_6") (pintype "passive"))
      (node (ref "IC9") (pin "13") (pinfunction "PH1(TXD2)_13") (pintype "bidirectional"))
    )
    (net (code "97") (name "/TXD3") (class "Default")
      (node (ref "COMMUNICATION1") (pin "8") (pinfunction "8_8") (pintype "passive"))
      (node (ref "IC9") (pin "64") (pinfunction "PJ1(TXD3/PCINT10)_64") (pintype "bidirectional"))
    )
    (net (code "98") (name "/TXLED") (class "Default")
      (node (ref "IC3") (pin "11") (pinfunction "(XCK)PD5_11") (pintype "bidirectional"))
      (node (ref "RN3") (pin "8") (pinfunction "2_8") (pintype "passive"))
    )
    (net (code "99") (name "/TXON") (class "Default")
      (node (ref "IC6") (pin "1") (pinfunction "TXN_1") (pintype "passive"))
      (node (ref "RN5") (pin "4") (pinfunction "1_4") (pintype "passive"))
      (node (ref "U1") (pin "P$6") (pinfunction "TX-_P$6") (pintype "bidirectional"))
    )
    (net (code "100") (name "/TXOP") (class "Default")
      (node (ref "IC6") (pin "2") (pinfunction "TXP_2") (pintype "passive"))
      (node (ref "RN5") (pin "3") (pinfunction "1_3") (pintype "passive"))
      (node (ref "U1") (pin "P$5") (pinfunction "TX+_P$5") (pintype "bidirectional"))
    )
    (net (code "101") (name "/USB+") (class "Default")
      (node (ref "F1") (pin "1") (pinfunction "1_1") (pintype "passive"))
      (node (ref "U$15") (pin "A4") (pinfunction "V+_A4") (pintype "power_in"))
      (node (ref "U$15") (pin "A9") (pinfunction "V+_A9") (pintype "power_in"))
      (node (ref "U$15") (pin "B4") (pinfunction "V+_B4") (pintype "power_in"))
      (node (ref "U$15") (pin "B9") (pinfunction "V+_B9") (pintype "power_in"))
    )
    (net (code "102") (name "/USBRXD") (class "Default")
      (node (ref "IC3") (pin "9") (pinfunction "(TXD1)PD3_9") (pintype "bidirectional"))
      (node (ref "RN3") (pin "5") (pinfunction "2_5") (pintype "passive"))
    )
    (net (code "103") (name "/USBTXD") (class "Default")
      (node (ref "IC3") (pin "8") (pinfunction "(RXD1)PD2_8") (pintype "bidirectional"))
      (node (ref "RN3") (pin "6") (pinfunction "2_6") (pintype "passive"))
    )
    (net (code "104") (name "/USBVCC") (class "Default")
      (node (ref "F1") (pin "2") (pinfunction "2_2") (pintype "passive"))
      (node (ref "IC3") (pin "31") (pinfunction "UVCC_31") (pintype "power_in"))
      (node (ref "JP5") (pin "1") (pinfunction "1_1") (pintype "passive"))
    )
    (net (code "105") (name "/VIN") (class "Default")
      (node (ref "C36") (pin "1") (pinfunction "1_1") (pintype "passive"))
      (node (ref "D1") (pin "C") (pinfunction "C_C") (pintype "passive"))
      (node (ref "IC1") (pin "2") (pinfunction "IN_2") (pintype "power_in"))
      (node (ref "JP3") (pin "4") (pinfunction "VIN[4]_4") (pintype "passive"))
      (node (ref "JP6") (pin "1") (pinfunction "1_1") (pintype "passive"))
      (node (ref "R10") (pin "1") (pinfunction "1_1") (pintype "passive"))
    )
    (net (code "106") (name "/WIZRST") (class "Default")
      (node (ref "IC2") (pin "2") (pinfunction "/RESET_2") (pintype "output"))
      (node (ref "IC6") (pin "37") (pinfunction "RST_N_37") (pintype "passive"))
      (node (ref "RN2") (pin "2") (pinfunction "1_2") (pintype "passive"))
    )
    (net (code "107") (name "/XTAL1") (class "Default")
      (node (ref "C21") (pin "2") (pinfunction "2_2") (pintype "passive"))
      (node (ref "IC9") (pin "34") (pinfunction "XTAL1_34") (pintype "input"))
      (node (ref "R7") (pin "1") (pinfunction "1_1") (pintype "passive"))
      (node (ref "X3") (pin "1") (pinfunction "1_1") (pintype "passive"))
    )
    (net (code "108") (name "/XTAL2") (class "Default")
      (node (ref "C20") (pin "2") (pinfunction "2_2") (pintype "passive"))
      (node (ref "IC9") (pin "33") (pinfunction "XTAL2_33") (pintype "output"))
      (node (ref "R7") (pin "2") (pinfunction "2_2") (pintype "passive"))
      (node (ref "X3") (pin "2") (pinfunction "2_2") (pintype "passive"))
    )
    (net (code "109") (name "/XTLN") (class "Default")
      (node (ref "C15") (pin "1") (pinfunction "1_1") (pintype "passive"))
      (node (ref "IC6") (pin "31") (pinfunction "XO_31") (pintype "passive"))
      (node (ref "R3") (pin "1") (pinfunction "1_1") (pintype "passive"))
      (node (ref "X2") (pin "1") (pinfunction "1_1") (pintype "passive"))
    )
    (net (code "110") (name "/XTLP") (class "Default")
      (node (ref "C16") (pin "1") (pinfunction "1_1") (pintype "passive"))
      (node (ref "IC6") (pin "30") (pinfunction "XI/CLKIN_30") (pintype "passive"))
      (node (ref "R3") (pin "2") (pinfunction "2_2") (pintype "passive"))
      (node (ref "X2") (pin "2") (pinfunction "2_2") (pintype "passive"))
    )
    (net (code "111") (name "3.3V") (class "Default")
      (node (ref "C10") (pin "A") (pinfunction "+_A") (pintype "passive"))
      (node (ref "JP6") (pin "5") (pinfunction "5_5") (pintype "passive"))
      (node (ref "L1") (pin "1") (pinfunction "1_1") (pintype "passive"))
      (node (ref "L2") (pin "1") (pinfunction "1_1") (pintype "passive"))
      (node (ref "LED7") (pin "A") (pinfunction "A_A") (pintype "passive"))
      (node (ref "LED8") (pin "A") (pinfunction "A_A") (pintype "passive"))
      (node (ref "REG1") (pin "2") (pinfunction "OUT_2") (pintype "output"))
      (node (ref "REG1") (pin "4") (pinfunction "OUT_4") (pintype "output"))
      (node (ref "REG2") (pin "2") (pinfunction "OUT_2") (pintype "output"))
      (node (ref "REG2") (pin "4") (pinfunction "OUT_4") (pintype "output"))
      (node (ref "U1") (pin "P$11") (pinfunction "Y+_P$11") (pintype "bidirectional"))
      (node (ref "U1") (pin "P$13") (pinfunction "G+_P$13") (pintype "bidirectional"))
    )
    (net (code "112") (name "5V") (class "Default")
      (node (ref "C12") (pin "1") (pinfunction "1_1") (pintype "passive"))
      (node (ref "C31") (pin "1") (pinfunction "1_1") (pintype "passive"))
      (node (ref "C33") (pin "1") (pinfunction "1_1") (pintype "passive"))
      (node (ref "C34") (pin "1") (pinfunction "1_1") (pintype "passive"))
      (node (ref "C6") (pin "2") (pinfunction "2_2") (pintype "passive"))
      (node (ref "C7") (pin "1") (pinfunction "1_1") (pintype "passive"))
      (node (ref "C9") (pin "1") (pinfunction "1_1") (pintype "passive"))
      (node (ref "IC2") (pin "4") (pinfunction "VCC_4") (pintype "power_in"))
      (node (ref "IC3") (pin "32") (pinfunction "AVCC_32") (pintype "power_in"))
      (node (ref "IC3") (pin "4") (pinfunction "VCC_4") (pintype "power_in"))
      (node (ref "IC4") (pin "6") (pinfunction "VCC_6") (pintype "power_in"))
      (node (ref "IC9") (pin "10") (pinfunction "VCC_10") (pintype "power_in"))
      (node (ref "IC9") (pin "100") (pinfunction "AVCC_100") (pintype "power_in"))
      (node (ref "IC9") (pin "31") (pinfunction "VCC1_31") (pintype "power_in"))
      (node (ref "IC9") (pin "61") (pinfunction "VCC2_61") (pintype "power_in"))
      (node (ref "IC9") (pin "80") (pinfunction "VCC3_80") (pintype "power_in"))
      (node (ref "ICSP") (pin "2") (pinfunction "2_2") (pintype "passive"))
      (node (ref "JP1") (pin "1") (pinfunction "1_1") (pintype "passive"))
      (node (ref "JP1") (pin "2") (pinfunction "2_2") (pintype "passive"))
      (node (ref "JP4") (pin "1") (pinfunction "1_1") (pintype "passive"))
      (node (ref "JP5") (pin "2") (pinfunction "2_2") (pintype "passive"))
      (node (ref "JP6") (pin "4") (pinfunction "4_4") (pintype "passive"))
      (node (ref "JP6") (pin "7") (pinfunction "7_7") (pintype "passive"))
      (node (ref "LED10") (pin "A") (pinfunction "A_A") (pintype "passive"))
      (node (ref "LED2") (pin "A") (pinfunction "A_A") (pintype "passive"))
      (node (ref "LED5") (pin "A") (pinfunction "A_A") (pintype "passive"))
      (node (ref "LED6") (pin "A") (pinfunction "A_A") (pintype "passive"))
      (node (ref "P3") (pin "2") (pinfunction "2_2") (pintype "passive"))
      (node (ref "R14") (pin "1") (pinfunction "1_1") (pintype "passive"))
      (node (ref "R15") (pin "1") (pinfunction "1_1") (pintype "passive"))
      (node (ref "R16") (pin "2") (pinfunction "2_2") (pintype "passive"))
      (node (ref "R17") (pin "2") (pinfunction "2_2") (pintype "passive"))
      (node (ref "REG1") (pin "3") (pinfunction "IN_3") (pintype "input"))
      (node (ref "REG2") (pin "3") (pinfunction "IN_3") (pintype "input"))
    )
    (net (code "113") (name "GND") (class "Default")
      (node (ref "C1") (pin "2") (pinfunction "2_2") (pintype "passive"))
      (node (ref "C10") (pin "C") (pinfunction "-_C") (pintype "passive"))
      (node (ref "C11") (pin "2") (pinfunction "2_2") (pintype "passive"))
      (node (ref "C12") (pin "2") (pinfunction "2_2") (pintype "passive"))
      (node (ref "C13") (pin "C") (pinfunction "-_C") (pintype "passive"))
      (node (ref "C14") (pin "2") (pinfunction "2_2") (pintype "passive"))
      (node (ref "C15") (pin "2") (pinfunction "2_2") (pintype "passive"))
      (node (ref "C16") (pin "2") (pinfunction "2_2") (pintype "passive"))
      (node (ref "C17") (pin "2") (pinfunction "2_2") (pintype "passive"))
      (node (ref "C2") (pin "1") (pinfunction "1_1") (pintype "passive"))
      (node (ref "C20") (pin "1") (pinfunction "1_1") (pintype "passive"))
      (node (ref "C21") (pin "1") (pinfunction "1_1") (pintype "passive"))
      (node (ref "C22") (pin "2") (pinfunction "2_2") (pintype "passive"))
      (node (ref "C23") (pin "2") (pinfunction "2_2") (pintype "passive"))
      (node (ref "C24") (pin "2") (pinfunction "2_2") (pintype "passive"))
      (node (ref "C27") (pin "2") (pinfunction "2_2") (pintype "passive"))
      (node (ref "C29") (pin "2") (pinfunction "2_2") (pintype "passive"))
      (node (ref "C3") (pin "C") (pinfunction "-_C") (pintype "passive"))
      (node (ref "C30") (pin "2") (pinfunction "2_2") (pintype "passive"))
      (node (ref "C31") (pin "2") (pinfunction "2_2") (pintype "passive"))
      (node (ref "C33") (pin "2") (pinfunction "2_2") (pintype "passive"))
      (node (ref "C34") (pin "2") (pinfunction "2_2") (pintype "passive"))
      (node (ref "C35") (pin "2") (pinfunction "2_2") (pintype "passive"))
      (node (ref "C36") (pin "2") (pinfunction "2_2") (pintype "passive"))
      (node (ref "C37") (pin "2") (pinfunction "2_2") (pintype "passive"))
      (node (ref "C4") (pin "C") (pinfunction "-_C") (pintype "passive"))
      (node (ref "C5") (pin "2") (pinfunction "2_2") (pintype "passive"))
      (node (ref "C6") (pin "1") (pinfunction "1_1") (pintype "passive"))
      (node (ref "C7") (pin "2") (pinfunction "2_2") (pintype "passive"))
      (node (ref "C8") (pin "1") (pinfunction "1_1") (pintype "passive"))
      (node (ref "C9") (pin "2") (pinfunction "2_2") (pintype "passive"))
      (node (ref "IC1") (pin "4") (pinfunction "GND_4") (pintype "power_in"))
      (node (ref "IC1") (pin "9") (pinfunction "TGND_9") (pintype "power_in"))
      (node (ref "IC2") (pin "1") (pinfunction "GND_1") (pintype "power_in"))
      (node (ref "IC3") (pin "28") (pinfunction "UGND_28") (pintype "power_in"))
      (node (ref "IC3") (pin "3") (pinfunction "GND_3") (pintype "power_in"))
      (node (ref "IC3") (pin "EXP") (pinfunction "PAD_EXP") (pintype "power_in"))
      (node (ref "IC4") (pin "2") (pinfunction "GND_2") (pintype "power_in"))
      (node (ref "IC4") (pin "4") (pinfunction "A1_4") (pintype "input"))
      (node (ref "IC4") (pin "5") (pinfunction "A0_5") (pintype "input"))
      (node (ref "IC6") (pin "14") (pinfunction "AGND_14") (pintype "passive"))
      (node (ref "IC6") (pin "16") (pinfunction "AGND_16") (pintype "passive"))
      (node (ref "IC6") (pin "19") (pinfunction "AGND_19") (pintype "passive"))
      (node (ref "IC6") (pin "29") (pinfunction "GND_29") (pintype "passive"))
      (node (ref "IC6") (pin "3") (pinfunction "AGND_3") (pintype "passive"))
      (node (ref "IC6") (pin "48") (pinfunction "AGND_48") (pintype "passive"))
      (node (ref "IC6") (pin "9") (pinfunction "AGND_9") (pintype "passive"))
      (node (ref "IC9") (pin "11") (pinfunction "GND_11") (pintype "power_in"))
      (node (ref "IC9") (pin "32") (pinfunction "GND1_32") (pintype "power_in"))
      (node (ref "IC9") (pin "62") (pinfunction "GND2_62") (pintype "power_in"))
      (node (ref "IC9") (pin "81") (pinfunction "GND3_81") (pintype "power_in"))
      (node (ref "IC9") (pin "99") (pinfunction "AGND_99") (pintype "power_in"))
      (node (ref "ICSP") (pin "6") (pinfunction "6_6") (pintype "passive"))
      (node (ref "J1") (pin "GND") (pinfunction "GND_GND") (pintype "bidirectional"))
      (node (ref "J1") (pin "GNDBREAK") (pinfunction "GNDBREAK_GNDBREAK") (pintype "bidirectional"))
      (node (ref "JP2") (pin "1") (pinfunction "1_1") (pintype "passive"))
      (node (ref "JP2") (pin "2") (pinfunction "2_2") (pintype "passive"))
      (node (ref "JP3") (pin "1") (pinfunction "GND[1]_1") (pintype "passive"))
      (node (ref "JP3") (pin "MNT1") (pinfunction "MNT1_MNT1") (pintype "passive"))
      (node (ref "JP3") (pin "MNT2") (pinfunction "MNT2_MNT2") (pintype "passive"))
      (node (ref "JP4") (pin "4") (pinfunction "4_4") (pintype "passive"))
      (node (ref "JP6") (pin "2") (pinfunction "2_2") (pintype "passive"))
      (node (ref "JP6") (pin "3") (pinfunction "3_3") (pintype "passive"))
      (node (ref "P3") (pin "6") (pinfunction "6_6") (pintype "passive"))
      (node (ref "P4") (pin "6") (pinfunction "GND_6") (pintype "bidirectional"))
      (node (ref "P4") (pin "GND1") (pinfunction "SHIELD1_GND1") (pintype "bidirectional"))
      (node (ref "P4") (pin "GND2") (pinfunction "SHIELD2_GND2") (pintype "bidirectional"))
      (node (ref "P4") (pin "GND3") (pinfunction "CD1_GND3") (pintype "bidirectional"))
      (node (ref "P4") (pin "GND4") (pinfunction "CD2_GND4") (pintype "bidirectional"))
      (node (ref "PWMH") (pin "7") (pinfunction "7_7") (pintype "passive"))
      (node (ref "Q2") (pin "2") (pinfunction "S_2") (pintype "passive"))
      (node (ref "R11") (pin "1") (pinfunction "1_1") (pintype "passive"))
      (node (ref "R13") (pin "1") (pinfunction "1_1") (pintype "passive"))
      (node (ref "R18") (pin "1") (pinfunction "1_1") (pintype "passive"))
      (node (ref "R19") (pin "1") (pinfunction "1_1") (pintype "passive"))
      (node (ref "R22") (pin "1") (pinfunction "1_1") (pintype "passive"))
      (node (ref "R6") (pin "1") (pinfunction "1_1") (pintype "passive"))
      (node (ref "REG1") (pin "1") (pinfunction "ADJ_1") (pintype "input"))
      (node (ref "REG2") (pin "1") (pinfunction "ADJ_1") (pintype "input"))
      (node (ref "RN1") (pin "5") (pinfunction "2_5") (pintype "passive"))
      (node (ref "RN1") (pin "6") (pinfunction "2_6") (pintype "passive"))
      (node (ref "RN1") (pin "7") (pinfunction "2_7") (pintype "passive"))
      (node (ref "RN1") (pin "8") (pinfunction "2_8") (pintype "passive"))
      (node (ref "RN2") (pin "8") (pinfunction "2_8") (pintype "passive"))
      (node (ref "RN8") (pin "1") (pinfunction "1_1") (pintype "passive"))
      (node (ref "RN8") (pin "2") (pinfunction "1_2") (pintype "passive"))
      (node (ref "RN8") (pin "3") (pinfunction "1_3") (pintype "passive"))
      (node (ref "S1") (pin "1") (pinfunction "1_1") (pintype "passive"))
      (node (ref "S1") (pin "2") (pinfunction "2_2") (pintype "passive"))
      (node (ref "SJ2") (pin "1") (pinfunction "1_1") (pintype "passive"))
      (node (ref "U$15") (pin "A1") (pinfunction "GND_A1") (pintype "power_in"))
      (node (ref "U$15") (pin "A12") (pinfunction "GND_A12") (pintype "power_in"))
      (node (ref "U$15") (pin "B1") (pinfunction "GND_B1") (pintype "power_in"))
      (node (ref "U$15") (pin "B12") (pinfunction "GND_B12") (pintype "power_in"))
      (node (ref "U$15") (pin "CASE1") (pinfunction "GND_CASE1") (pintype "power_in"))
      (node (ref "U$15") (pin "CASE2") (pinfunction "GND_CASE2") (pintype "power_in"))
      (node (ref "U$15") (pin "CASE3") (pinfunction "GND_CASE3") (pintype "power_in"))
      (node (ref "U$15") (pin "CASE4") (pinfunction "GND_CASE4") (pintype "power_in"))
      (node (ref "U$15") (pin "FIX1") (pinfunction "GND_FIX1") (pintype "power_in"))
      (node (ref "U$15") (pin "FIX2") (pinfunction "GND_FIX2") (pintype "power_in"))
      (node (ref "U$15") (pin "FIX3") (pinfunction "GND_FIX3") (pintype "power_in"))
      (node (ref "U$15") (pin "FIX4") (pinfunction "GND_FIX4") (pintype "power_in"))
      (node (ref "U1") (pin "GND1") (pinfunction "GND1_GND1") (pintype "bidirectional"))
      (node (ref "U1") (pin "GND2") (pinfunction "GND2_GND2") (pintype "bidirectional"))
      (node (ref "Z1") (pin "2") (pinfunction "2_2") (pintype "passive"))
      (node (ref "Z2") (pin "2") (pinfunction "2_2") (pintype "passive"))
    )
    (net (code "114") (name "Net-(C1-Pad1)") (class "Default")
      (node (ref "C1") (pin "1") (pinfunction "1_1") (pintype "passive"))
      (node (ref "R9") (pin "1") (pinfunction "1_1") (pintype "passive"))
    )
    (net (code "115") (name "Net-(C3-+)") (class "Default")
      (node (ref "C3") (pin "A") (pinfunction "+_A") (pintype "passive"))
      (node (ref "IC6") (pin "20") (pinfunction "TOCAP_20") (pintype "passive"))
    )
    (net (code "116") (name "Net-(C8-Pad2)") (class "Default")
      (node (ref "C8") (pin "2") (pinfunction "2_2") (pintype "passive"))
      (node (ref "R1") (pin "1") (pinfunction "1_1") (pintype "passive"))
      (node (ref "R2") (pin "2") (pinfunction "2_2") (pintype "passive"))
      (node (ref "X1") (pin "1") (pinfunction "1_1") (pintype "passive"))
    )
    (net (code "117") (name "Net-(C19-Pad1)") (class "Default")
      (node (ref "C19") (pin "1") (pinfunction "1_1") (pintype "passive"))
      (node (ref "JP7") (pin "1") (pinfunction "1_1") (pintype "passive"))
      (node (ref "SJ3") (pin "2") (pinfunction "2_2") (pintype "passive"))
    )
    (net (code "118") (name "Net-(D1-PadA)") (class "Default")
      (node (ref "D1") (pin "A") (pinfunction "A_A") (pintype "passive"))
      (node (ref "J1") (pin "PWR") (pinfunction "PWR_PWR") (pintype "bidirectional"))
    )
    (net (code "119") (name "Net-(IC1-BS)") (class "Default")
      (node (ref "C32") (pin "2") (pinfunction "2_2") (pintype "passive"))
      (node (ref "IC1") (pin "1") (pinfunction "BS_1") (pintype "bidirectional"))
    )
    (net (code "120") (name "Net-(IC1-COMP)") (class "Default")
      (node (ref "C35") (pin "1") (pinfunction "1_1") (pintype "passive"))
      (node (ref "IC1") (pin "6") (pinfunction "COMP_6") (pintype "bidirectional"))
      (node (ref "R9") (pin "2") (pinfunction "2_2") (pintype "passive"))
    )
    (net (code "121") (name "Net-(IC1-EN)") (class "Default")
      (node (ref "IC1") (pin "7") (pinfunction "EN_7") (pintype "input"))
      (node (ref "R10") (pin "2") (pinfunction "2_2") (pintype "passive"))
    )
    (net (code "122") (name "Net-(IC1-FB)") (class "Default")
      (node (ref "IC1") (pin "5") (pinfunction "FB_5") (pintype "bidirectional"))
      (node (ref "R11") (pin "2") (pinfunction "2_2") (pintype "passive"))
      (node (ref "R12") (pin "1") (pinfunction "1_1") (pintype "passive"))
    )
    (net (code "123") (name "Net-(IC1-SS)") (class "Default")
      (node (ref "C27") (pin "1") (pinfunction "1_1") (pintype "passive"))
      (node (ref "IC1") (pin "8") (pinfunction "SS_8") (pintype "bidirectional"))
    )
    (net (code "124") (name "Net-(IC1-SW)") (class "Default")
      (node (ref "C32") (pin "1") (pinfunction "1_1") (pintype "passive"))
      (node (ref "IC1") (pin "3") (pinfunction "SW_3") (pintype "bidirectional"))
      (node (ref "L4") (pin "1") (pinfunction "1_1") (pintype "bidirectional"))
    )
    (net (code "125") (name "Net-(IC3-UCAP)") (class "Default")
      (node (ref "C11") (pin "1") (pinfunction "1_1") (pintype "passive"))
      (node (ref "IC3") (pin "27") (pinfunction "UCAP_27") (pintype "passive"))
    )
    (net (code "126") (name "Net-(IC3-XTAL1)") (class "Default")
      (node (ref "IC3") (pin "1") (pinfunction "XTAL1_1") (pintype "bidirectional"))
      (node (ref "R2") (pin "1") (pinfunction "1_1") (pintype "passive"))
    )
    (net (code "127") (name "Net-(IC3-XTAL2)") (class "Default")
      (node (ref "C2") (pin "2") (pinfunction "2_2") (pintype "passive"))
      (node (ref "IC3") (pin "2") (pinfunction "XTAL2_2") (pintype "bidirectional"))
      (node (ref "R1") (pin "2") (pinfunction "2_2") (pintype "passive"))
      (node (ref "X1") (pin "2") (pinfunction "2_2") (pintype "passive"))
    )
    (net (code "128") (name "Net-(IC4-SCL)") (class "Default")
      (node (ref "IC4") (pin "1") (pinfunction "SCL_1") (pintype "bidirectional"))
      (node (ref "R15") (pin "2") (pinfunction "2_2") (pintype "passive"))
      (node (ref "SJ6") (pin "2") (pinfunction "2_2") (pintype "passive"))
    )
    (net (code "129") (name "Net-(IC4-SDA)") (class "Default")
      (node (ref "IC4") (pin "3") (pinfunction "SDA_3") (pintype "bidirectional"))
      (node (ref "R14") (pin "2") (pinfunction "2_2") (pintype "passive"))
      (node (ref "SJ5") (pin "2") (pinfunction "2_2") (pintype "passive"))
    )
    (net (code "130") (name "Net-(IC6-1V2O)") (class "Default")
      (node (ref "C5") (pin "1") (pinfunction "1_1") (pintype "passive"))
      (node (ref "IC6") (pin "22") (pinfunction "1V2O_22") (pintype "passive"))
    )
    (net (code "131") (name "Net-(IC6-RSVD-Pad23)") (class "Default")
      (node (ref "IC6") (pin "23") (pinfunction "RSVD_23") (pintype "passive"))
      (node (ref "R22") (pin "2") (pinfunction "2_2") (pintype "passive"))
    )
    (net (code "132") (name "Net-(IC6-RSVD-Pad38)") (class "Default")
      (node (ref "IC6") (pin "38") (pinfunction "RSVD_38") (pintype "passive"))
      (node (ref "RN2") (pin "1") (pinfunction "1_1") (pintype "passive"))
    )
    (net (code "133") (name "Net-(IC6-RSVD-Pad42)") (class "Default")
      (node (ref "IC6") (pin "42") (pinfunction "RSVD_42") (pintype "passive"))
      (node (ref "RN1") (pin "1") (pinfunction "1_1") (pintype "passive"))
    )
    (net (code "134") (name "Net-(JP3-V+[3])") (class "Default")
      (node (ref "JP3") (pin "3") (pinfunction "V+[3]_3") (pintype "passive"))
      (node (ref "U1") (pin "P$9") (pinfunction "V+_P$9") (pintype "bidirectional"))
    )
    (net (code "135") (name "Net-(JP3-V-[2])") (class "Default")
      (node (ref "JP3") (pin "2") (pinfunction "V-[2]_2") (pintype "passive"))
      (node (ref "U1") (pin "P$10") (pinfunction "V-_P$10") (pintype "bidirectional"))
    )
    (net (code "136") (name "Net-(LED2-PadC)") (class "Default")
      (node (ref "LED2") (pin "C") (pinfunction "C_C") (pintype "passive"))
      (node (ref "R13") (pin "2") (pinfunction "2_2") (pintype "passive"))
    )
    (net (code "137") (name "Net-(LED5-PadC)") (class "Default")
      (node (ref "LED5") (pin "C") (pinfunction "C_C") (pintype "passive"))
      (node (ref "RN3") (pin "1") (pinfunction "1_1") (pintype "passive"))
    )
    (net (code "138") (name "Net-(LED10-PadC)") (class "Default")
      (node (ref "LED10") (pin "C") (pinfunction "C_C") (pintype "passive"))
      (node (ref "R8") (pin "2") (pinfunction "2_2") (pintype "passive"))
    )
    (net (code "139") (name "Net-(P4-CS)") (class "Default")
      (node (ref "P4") (pin "2") (pinfunction "CS_2") (pintype "bidirectional"))
      (node (ref "RN6") (pin "2") (pinfunction "1_2") (pintype "passive"))
      (node (ref "RN8") (pin "8") (pinfunction "2_8") (pintype "passive"))
    )
    (net (code "140") (name "Net-(P4-DI)") (class "Default")
      (node (ref "P4") (pin "3") (pinfunction "DI_3") (pintype "bidirectional"))
      (node (ref "RN6") (pin "3") (pinfunction "1_3") (pintype "passive"))
      (node (ref "RN8") (pin "7") (pinfunction "2_7") (pintype "passive"))
    )
    (net (code "141") (name "Net-(P4-SCK)") (class "Default")
      (node (ref "P4") (pin "5") (pinfunction "SCK_5") (pintype "bidirectional"))
      (node (ref "RN6") (pin "4") (pinfunction "1_4") (pintype "passive"))
      (node (ref "RN8") (pin "6") (pinfunction "2_6") (pintype "passive"))
    )
    (net (code "142") (name "Net-(Q2-D)") (class "Default")
      (node (ref "Q2") (pin "3") (pinfunction "D_3") (pintype "passive"))
      (node (ref "R8") (pin "1") (pinfunction "1_1") (pintype "passive"))
    )
    (net (code "143") (name "Net-(RN1B-1)") (class "Default")
      (node (ref "IC6") (pin "41") (pinfunction "RSVD_41") (pintype "passive"))
      (node (ref "RN1") (pin "2") (pinfunction "1_2") (pintype "passive"))
    )
    (net (code "144") (name "Net-(RN1C-1)") (class "Default")
      (node (ref "IC6") (pin "40") (pinfunction "RSVD_40") (pintype "passive"))
      (node (ref "RN1") (pin "3") (pinfunction "1_3") (pintype "passive"))
    )
    (net (code "145") (name "Net-(RN1D-1)") (class "Default")
      (node (ref "IC6") (pin "39") (pinfunction "RSVD_39") (pintype "passive"))
      (node (ref "RN1") (pin "4") (pinfunction "1_4") (pintype "passive"))
    )
    (net (code "146") (name "Net-(RN3B-1)") (class "Default")
      (node (ref "LED6") (pin "C") (pinfunction "C_C") (pintype "passive"))
      (node (ref "RN3") (pin "2") (pinfunction "1_2") (pintype "passive"))
    )
    (net (code "147") (name "Net-(RN5A-2)") (class "Default")
      (node (ref "C23") (pin "1") (pinfunction "1_1") (pintype "passive"))
      (node (ref "RN5") (pin "7") (pinfunction "2_7") (pintype "passive"))
      (node (ref "RN5") (pin "8") (pinfunction "2_8") (pintype "passive"))
    )
    (net (code "148") (name "Net-(RN5C-2)") (class "Default")
      (node (ref "C24") (pin "1") (pinfunction "1_1") (pintype "passive"))
      (node (ref "RN5") (pin "5") (pinfunction "2_5") (pintype "passive"))
      (node (ref "RN5") (pin "6") (pinfunction "2_6") (pintype "passive"))
    )
    (net (code "149") (name "Net-(RN9A-2)") (class "Default")
      (node (ref "RN9") (pin "8") (pinfunction "2_8") (pintype "passive"))
      (node (ref "U1") (pin "P$12") (pinfunction "Y-_P$12") (pintype "bidirectional"))
    )
    (net (code "150") (name "Net-(RN9B-2)") (class "Default")
      (node (ref "LED7") (pin "C") (pinfunction "C_C") (pintype "passive"))
      (node (ref "RN9") (pin "7") (pinfunction "2_7") (pintype "passive"))
    )
    (net (code "151") (name "Net-(RN9C-2)") (class "Default")
      (node (ref "RN9") (pin "6") (pinfunction "2_6") (pintype "passive"))
      (node (ref "U1") (pin "P$14") (pinfunction "G-_P$14") (pintype "bidirectional"))
    )
    (net (code "152") (name "Net-(RN9D-2)") (class "Default")
      (node (ref "LED8") (pin "C") (pinfunction "C_C") (pintype "passive"))
      (node (ref "RN9") (pin "5") (pinfunction "2_5") (pintype "passive"))
    )
    (net (code "153") (name "Net-(U$15-CC1)") (class "Default")
      (node (ref "R19") (pin "2") (pinfunction "2_2") (pintype "passive"))
      (node (ref "U$15") (pin "A5") (pinfunction "CC1_A5") (pintype "bidirectional"))
    )
    (net (code "154") (name "Net-(U$15-CC2)") (class "Default")
      (node (ref "R18") (pin "2") (pinfunction "2_2") (pintype "passive"))
      (node (ref "U$15") (pin "B5") (pinfunction "CC2_B5") (pintype "bidirectional"))
    )
    (net (code "155") (name "unconnected-(IC3-(RTS)PD6-Pad12)") (class "Default")
      (node (ref "IC3") (pin "12") (pinfunction "(RTS)PD6_12") (pintype "bidirectional"))
    )
    (net (code "156") (name "unconnected-(IC3-(SS)PB0-Pad14)") (class "Default")
      (node (ref "IC3") (pin "14") (pinfunction "(SS)PB0_14") (pintype "bidirectional"))
    )
    (net (code "157") (name "unconnected-(IC3-PB4-Pad18)") (class "Default")
      (node (ref "IC3") (pin "18") (pinfunction "PB4_18") (pintype "bidirectional"))
    )
    (net (code "158") (name "unconnected-(IC3-PB5-Pad19)") (class "Default")
      (node (ref "IC3") (pin "19") (pinfunction "PB5_19") (pintype "bidirectional"))
    )
    (net (code "159") (name "unconnected-(IC3-PB6-Pad20)") (class "Default")
      (node (ref "IC3") (pin "20") (pinfunction "PB6_20") (pintype "bidirectional"))
    )
    (net (code "160") (name "unconnected-(IC3-PB7-Pad21)") (class "Default")
      (node (ref "IC3") (pin "21") (pinfunction "PB7_21") (pintype "bidirectional"))
    )
    (net (code "161") (name "unconnected-(IC3-PC2-Pad5)") (class "Default")
      (node (ref "IC3") (pin "5") (pinfunction "PC2_5") (pintype "bidirectional"))
    )
    (net (code "162") (name "unconnected-(IC3-PC4-Pad26)") (class "Default")
      (node (ref "IC3") (pin "26") (pinfunction "PC4_26") (pintype "bidirectional"))
    )
    (net (code "163") (name "unconnected-(IC3-PC5-Pad25)") (class "Default")
      (node (ref "IC3") (pin "25") (pinfunction "PC5_25") (pintype "bidirectional"))
    )
    (net (code "164") (name "unconnected-(IC3-PC6-Pad23)") (class "Default")
      (node (ref "IC3") (pin "23") (pinfunction "PC6_23") (pintype "bidirectional"))
    )
    (net (code "165") (name "unconnected-(IC3-PC7-Pad22)") (class "Default")
      (node (ref "IC3") (pin "22") (pinfunction "PC7_22") (pintype "bidirectional"))
    )
    (net (code "166") (name "unconnected-(IC3-PD0-Pad6)") (class "Default")
      (node (ref "IC3") (pin "6") (pinfunction "PD0_6") (pintype "bidirectional"))
    )
    (net (code "167") (name "unconnected-(IC3-PD1-Pad7)") (class "Default")
      (node (ref "IC3") (pin "7") (pinfunction "PD1_7") (pintype "bidirectional"))
    )
    (net (code "168") (name "unconnected-(IC6-DNC-Pad7)") (class "Default")
      (node (ref "IC6") (pin "7") (pinfunction "DNC_7") (pintype "passive"))
    )
    (net (code "169") (name "unconnected-(IC6-NC-Pad12)") (class "Default")
      (node (ref "IC6") (pin "12") (pinfunction "NC_12") (pintype "passive"))
    )
    (net (code "170") (name "unconnected-(IC6-NC-Pad13)") (class "Default")
      (node (ref "IC6") (pin "13") (pinfunction "NC_13") (pintype "passive"))
    )
    (net (code "171") (name "unconnected-(IC6-NC-Pad46)") (class "Default")
      (node (ref "IC6") (pin "46") (pinfunction "NC_46") (pintype "passive"))
    )
    (net (code "172") (name "unconnected-(IC6-NC-Pad47)") (class "Default")
      (node (ref "IC6") (pin "47") (pinfunction "NC_47") (pintype "passive"))
    )
    (net (code "173") (name "unconnected-(IC6-VBG-Pad18)") (class "Default")
      (node (ref "IC6") (pin "18") (pinfunction "VBG_18") (pintype "passive"))
    )
    (net (code "174") (name "unconnected-(IC9-(CLKO{slash}ICP3{slash}INT7)PE7-Pad9)") (class "Default")
      (node (ref "IC9") (pin "9") (pinfunction "(CLKO/ICP3/INT7)PE7_9") (pintype "bidirectional"))
    )
    (net (code "175") (name "unconnected-(IC9-(ICP1)PD4-Pad47)") (class "Default")
      (node (ref "IC9") (pin "47") (pinfunction "(ICP1)PD4_47") (pintype "bidirectional"))
    )
    (net (code "176") (name "unconnected-(IC9-(T1)PD6-Pad49)") (class "Default")
      (node (ref "IC9") (pin "49") (pinfunction "(T1)PD6_49") (pintype "bidirectional"))
    )
    (net (code "177") (name "unconnected-(IC9-(T3{slash}INT6)PE6-Pad8)") (class "Default")
      (node (ref "IC9") (pin "8") (pinfunction "(T3/INT6)PE6_8") (pintype "bidirectional"))
    )
    (net (code "178") (name "unconnected-(IC9-(TOSC1)PG4-Pad29)") (class "Default")
      (node (ref "IC9") (pin "29") (pinfunction "(TOSC1)PG4_29") (pintype "bidirectional"))
    )
    (net (code "179") (name "unconnected-(IC9-(TOSC2)PG3-Pad28)") (class "Default")
      (node (ref "IC9") (pin "28") (pinfunction "(TOSC2)PG3_28") (pintype "bidirectional"))
    )
    (net (code "180") (name "unconnected-(IC9-(XCK0{slash}AIN0)PE2-Pad4)") (class "Default")
      (node (ref "IC9") (pin "4") (pinfunction "(XCK0/AIN0)PE2_4") (pintype "bidirectional"))
    )
    (net (code "181") (name "unconnected-(IC9-(XCK1)PD5-Pad48)") (class "Default")
      (node (ref "IC9") (pin "48") (pinfunction "(XCK1)PD5_48") (pintype "bidirectional"))
    )
    (net (code "182") (name "unconnected-(IC9-PH2(XCK2)-Pad14)") (class "Default")
      (node (ref "IC9") (pin "14") (pinfunction "PH2(XCK2)_14") (pintype "bidirectional"))
    )
    (net (code "183") (name "unconnected-(IC9-PH7(T4)-Pad27)") (class "Default")
      (node (ref "IC9") (pin "27") (pinfunction "PH7(T4)_27") (pintype "bidirectional"))
    )
    (net (code "184") (name "unconnected-(IC9-PJ2(XCK3{slash}PCINT11)-Pad65)") (class "Default")
      (node (ref "IC9") (pin "65") (pinfunction "PJ2(XCK3/PCINT11)_65") (pintype "bidirectional"))
    )
    (net (code "185") (name "unconnected-(IC9-PJ3(PCINT12)-Pad66)") (class "Default")
      (node (ref "IC9") (pin "66") (pinfunction "PJ3(PCINT12)_66") (pintype "bidirectional"))
    )
    (net (code "186") (name "unconnected-(IC9-PJ4(PCINT13)-Pad67)") (class "Default")
      (node (ref "IC9") (pin "67") (pinfunction "PJ4(PCINT13)_67") (pintype "bidirectional"))
    )
    (net (code "187") (name "unconnected-(IC9-PJ5(PCINT14)-Pad68)") (class "Default")
      (node (ref "IC9") (pin "68") (pinfunction "PJ5(PCINT14)_68") (pintype "bidirectional"))
    )
    (net (code "188") (name "unconnected-(IC9-PJ6(PCINT15)-Pad69)") (class "Default")
      (node (ref "IC9") (pin "69") (pinfunction "PJ6(PCINT15)_69") (pintype "bidirectional"))
    )
    (net (code "189") (name "unconnected-(IC9-PJ7-Pad79)") (class "Default")
      (node (ref "IC9") (pin "79") (pinfunction "PJ7_79") (pintype "bidirectional"))
    )
    (net (code "190") (name "unconnected-(P4-NC-Pad1)") (class "Default")
      (node (ref "P4") (pin "1") (pinfunction "NC_1") (pintype "bidirectional"))
    )
    (net (code "191") (name "unconnected-(P4-RSV-Pad8)") (class "Default")
      (node (ref "P4") (pin "8") (pinfunction "RSV_8") (pintype "bidirectional"))
    )
    (net (code "192") (name "unconnected-(RN6-Pad1)") (class "Default")
      (node (ref "RN6") (pin "1") (pinfunction "1_1") (pintype "passive"))
    )
    (net (code "193") (name "unconnected-(RN6A-2-Pad8)") (class "Default")
      (node (ref "RN6") (pin "8") (pinfunction "2_8") (pintype "passive"))
    )
    (net (code "194") (name "unconnected-(RN8D-1-Pad4)") (class "Default")
      (node (ref "RN8") (pin "4") (pinfunction "1_4") (pintype "passive"))
    )
    (net (code "195") (name "unconnected-(RN8D-2-Pad5)") (class "Default")
      (node (ref "RN8") (pin "5") (pinfunction "2_5") (pintype "passive"))
    )
    (net (code "196") (name "unconnected-(U$15-RX1+-PadB11)") (class "Default")
      (node (ref "U$15") (pin "B11") (pinfunction "RX1+_B11") (pintype "bidirectional"))
    )
    (net (code "197") (name "unconnected-(U$15-RX1--PadB10)") (class "Default")
      (node (ref "U$15") (pin "B10") (pinfunction "RX1-_B10") (pintype "bidirectional"))
    )
    (net (code "198") (name "unconnected-(U$15-RX2+-PadA11)") (class "Default")
      (node (ref "U$15") (pin "A11") (pinfunction "RX2+_A11") (pintype "bidirectional"))
    )
    (net (code "199") (name "unconnected-(U$15-RX2--PadA10)") (class "Default")
      (node (ref "U$15") (pin "A10") (pinfunction "RX2-_A10") (pintype "bidirectional"))
    )
    (net (code "200") (name "unconnected-(U$15-SBU1-PadA8)") (class "Default")
      (node (ref "U$15") (pin "A8") (pinfunction "SBU1_A8") (pintype "bidirectional"))
    )
    (net (code "201") (name "unconnected-(U$15-SBU2-PadB8)") (class "Default")
      (node (ref "U$15") (pin "B8") (pinfunction "SBU2_B8") (pintype "bidirectional"))
    )
    (net (code "202") (name "unconnected-(U$15-TX1+-PadA2)") (class "Default")
      (node (ref "U$15") (pin "A2") (pinfunction "TX1+_A2") (pintype "bidirectional"))
    )
    (net (code "203") (name "unconnected-(U$15-TX1--PadA3)") (class "Default")
      (node (ref "U$15") (pin "A3") (pinfunction "TX1-_A3") (pintype "bidirectional"))
    )
    (net (code "204") (name "unconnected-(U$15-TX2+-PadB2)") (class "Default")
      (node (ref "U$15") (pin "B2") (pinfunction "TX2+_B2") (pintype "bidirectional"))
    )
    (net (code "205") (name "unconnected-(U$15-TX2--PadB3)") (class "Default")
      (node (ref "U$15") (pin "B3") (pinfunction "TX2-_B3") (pintype "bidirectional"))
    )
  )
)
